# axiom_beta_sensor_cmv12000_tht_v0_16_r1_.net
KiCad netlist of a schematic drawn in EAGLE
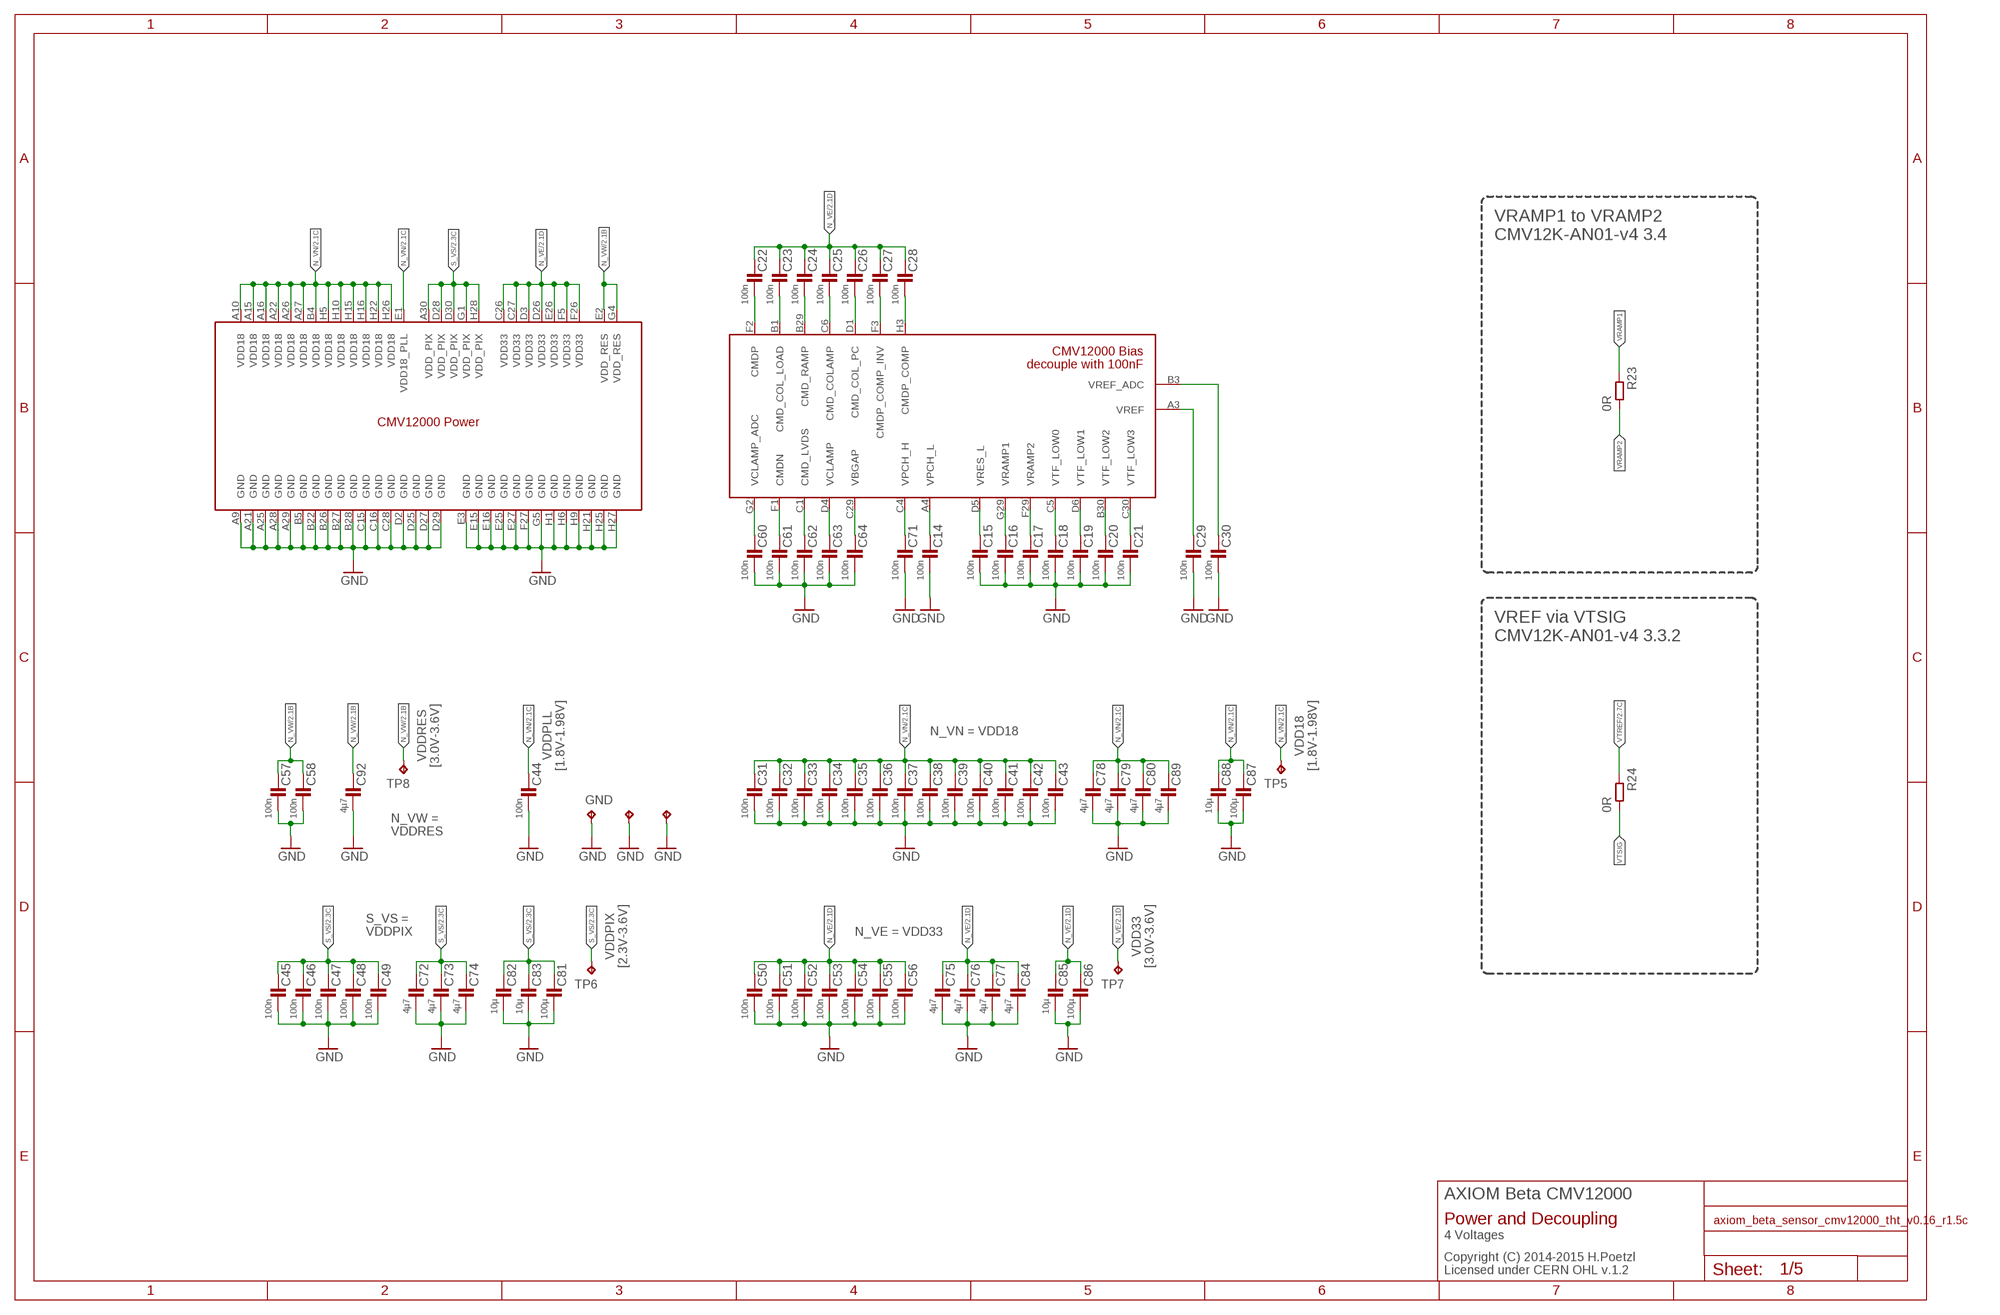
[diagram p0: schematic, sheet 1]
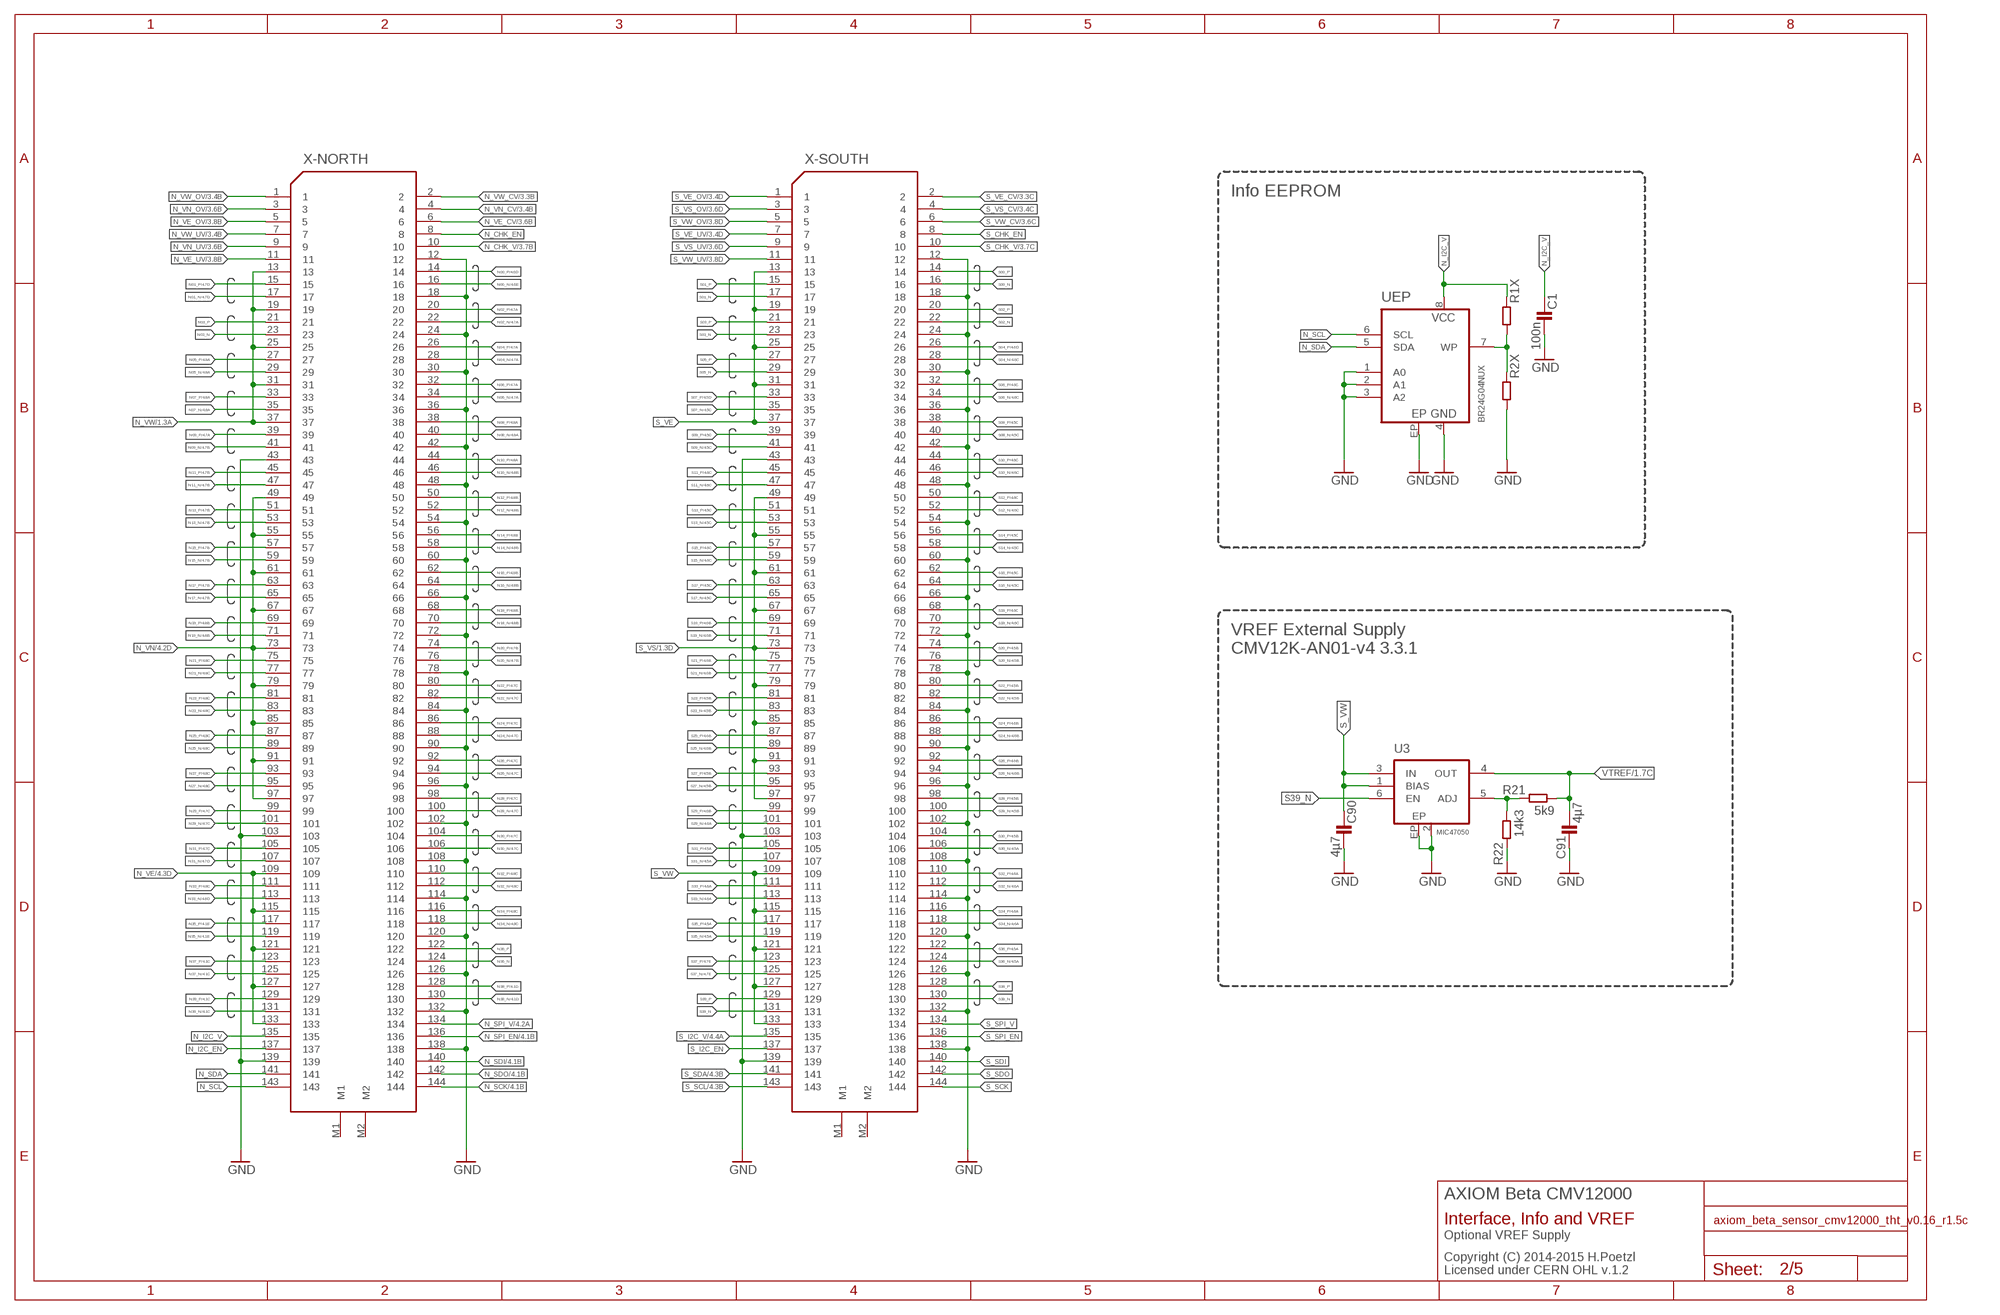
[diagram p1: schematic, sheet 2]
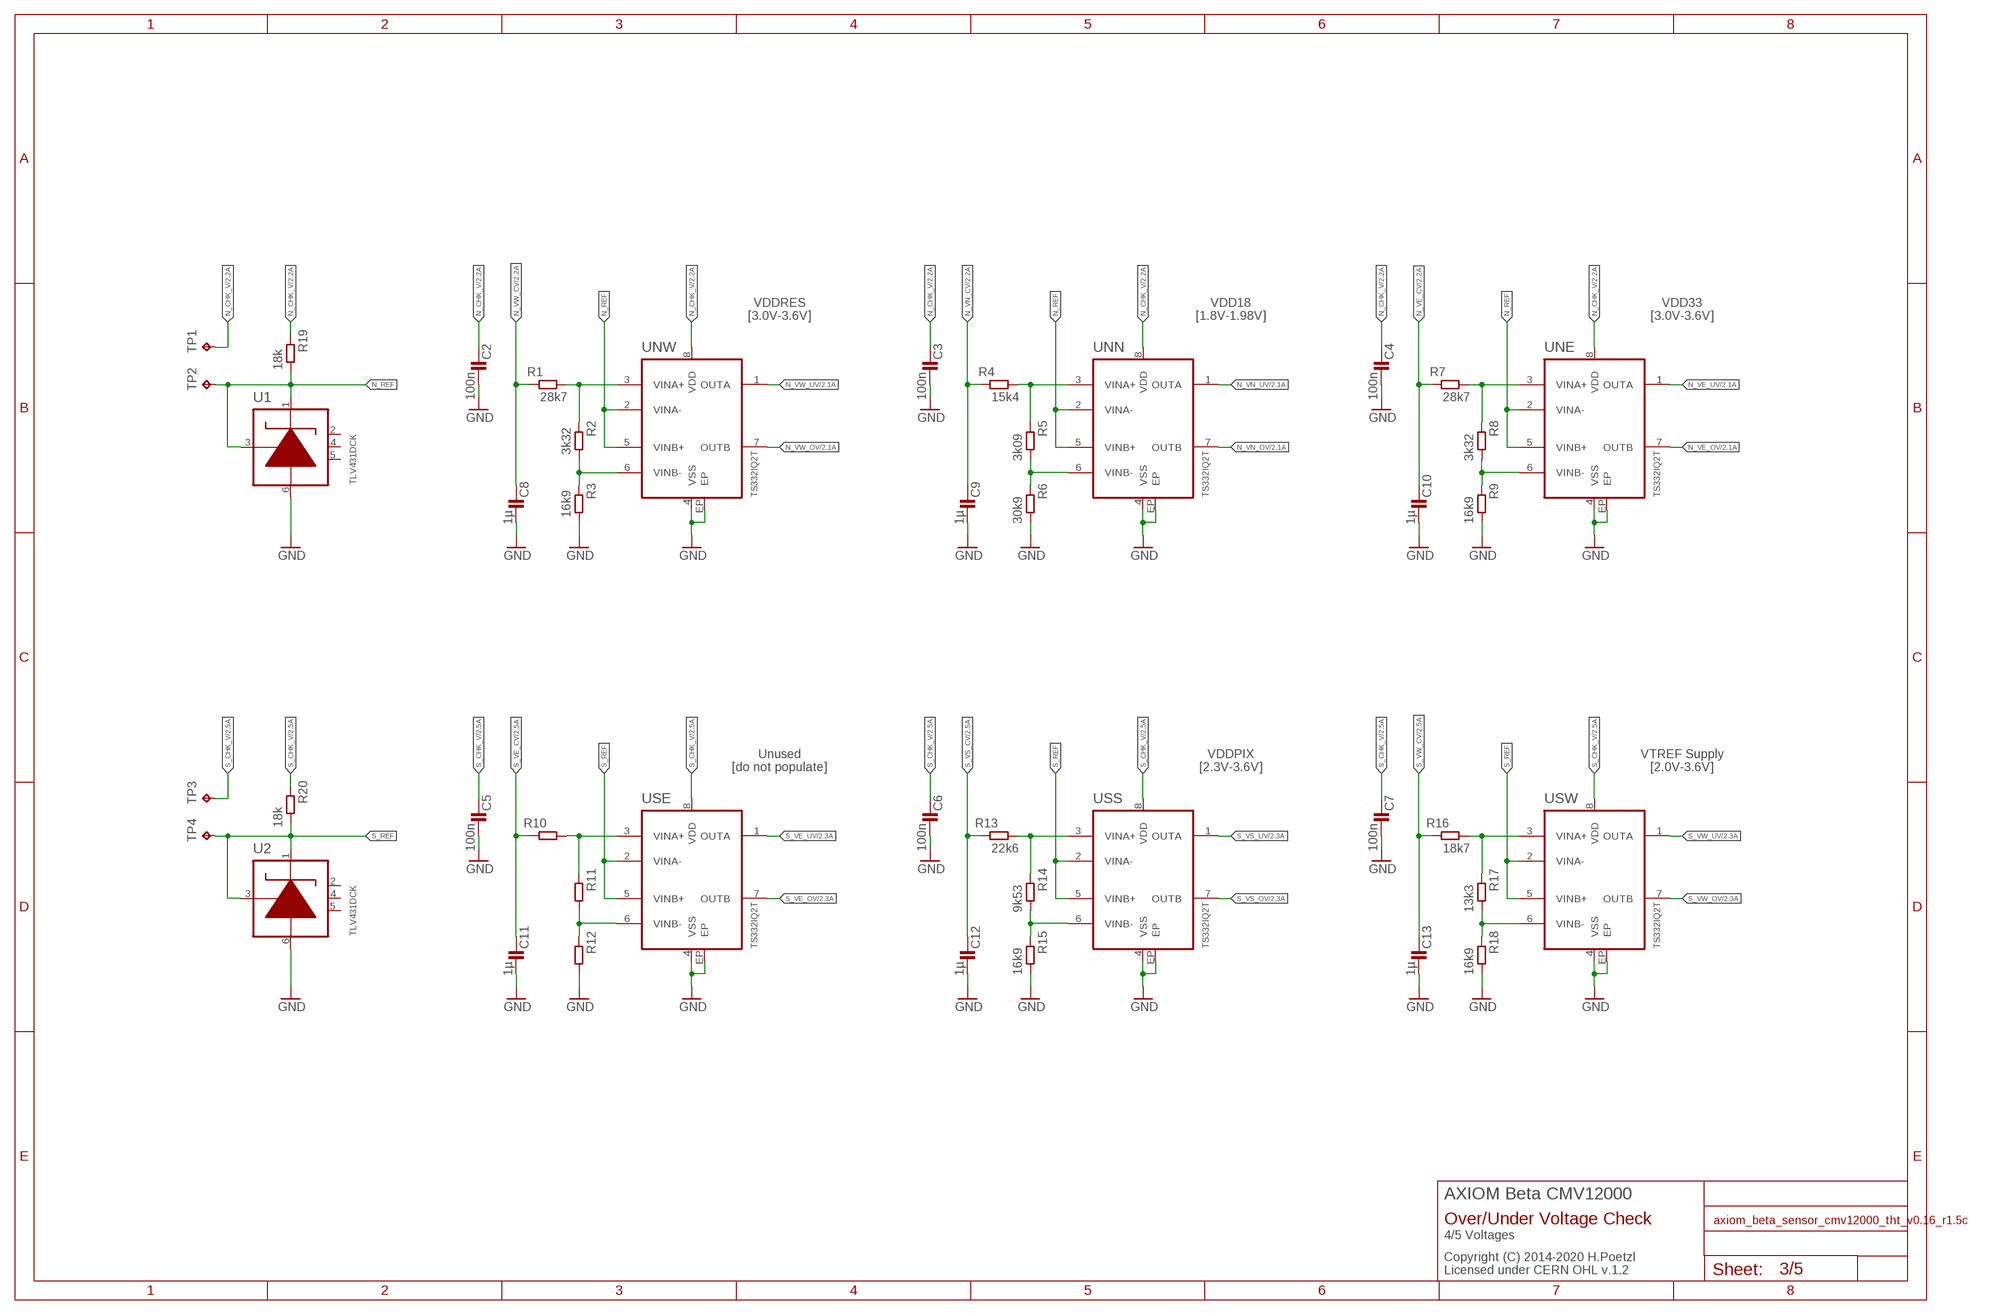
[diagram p2: schematic, sheet 3]
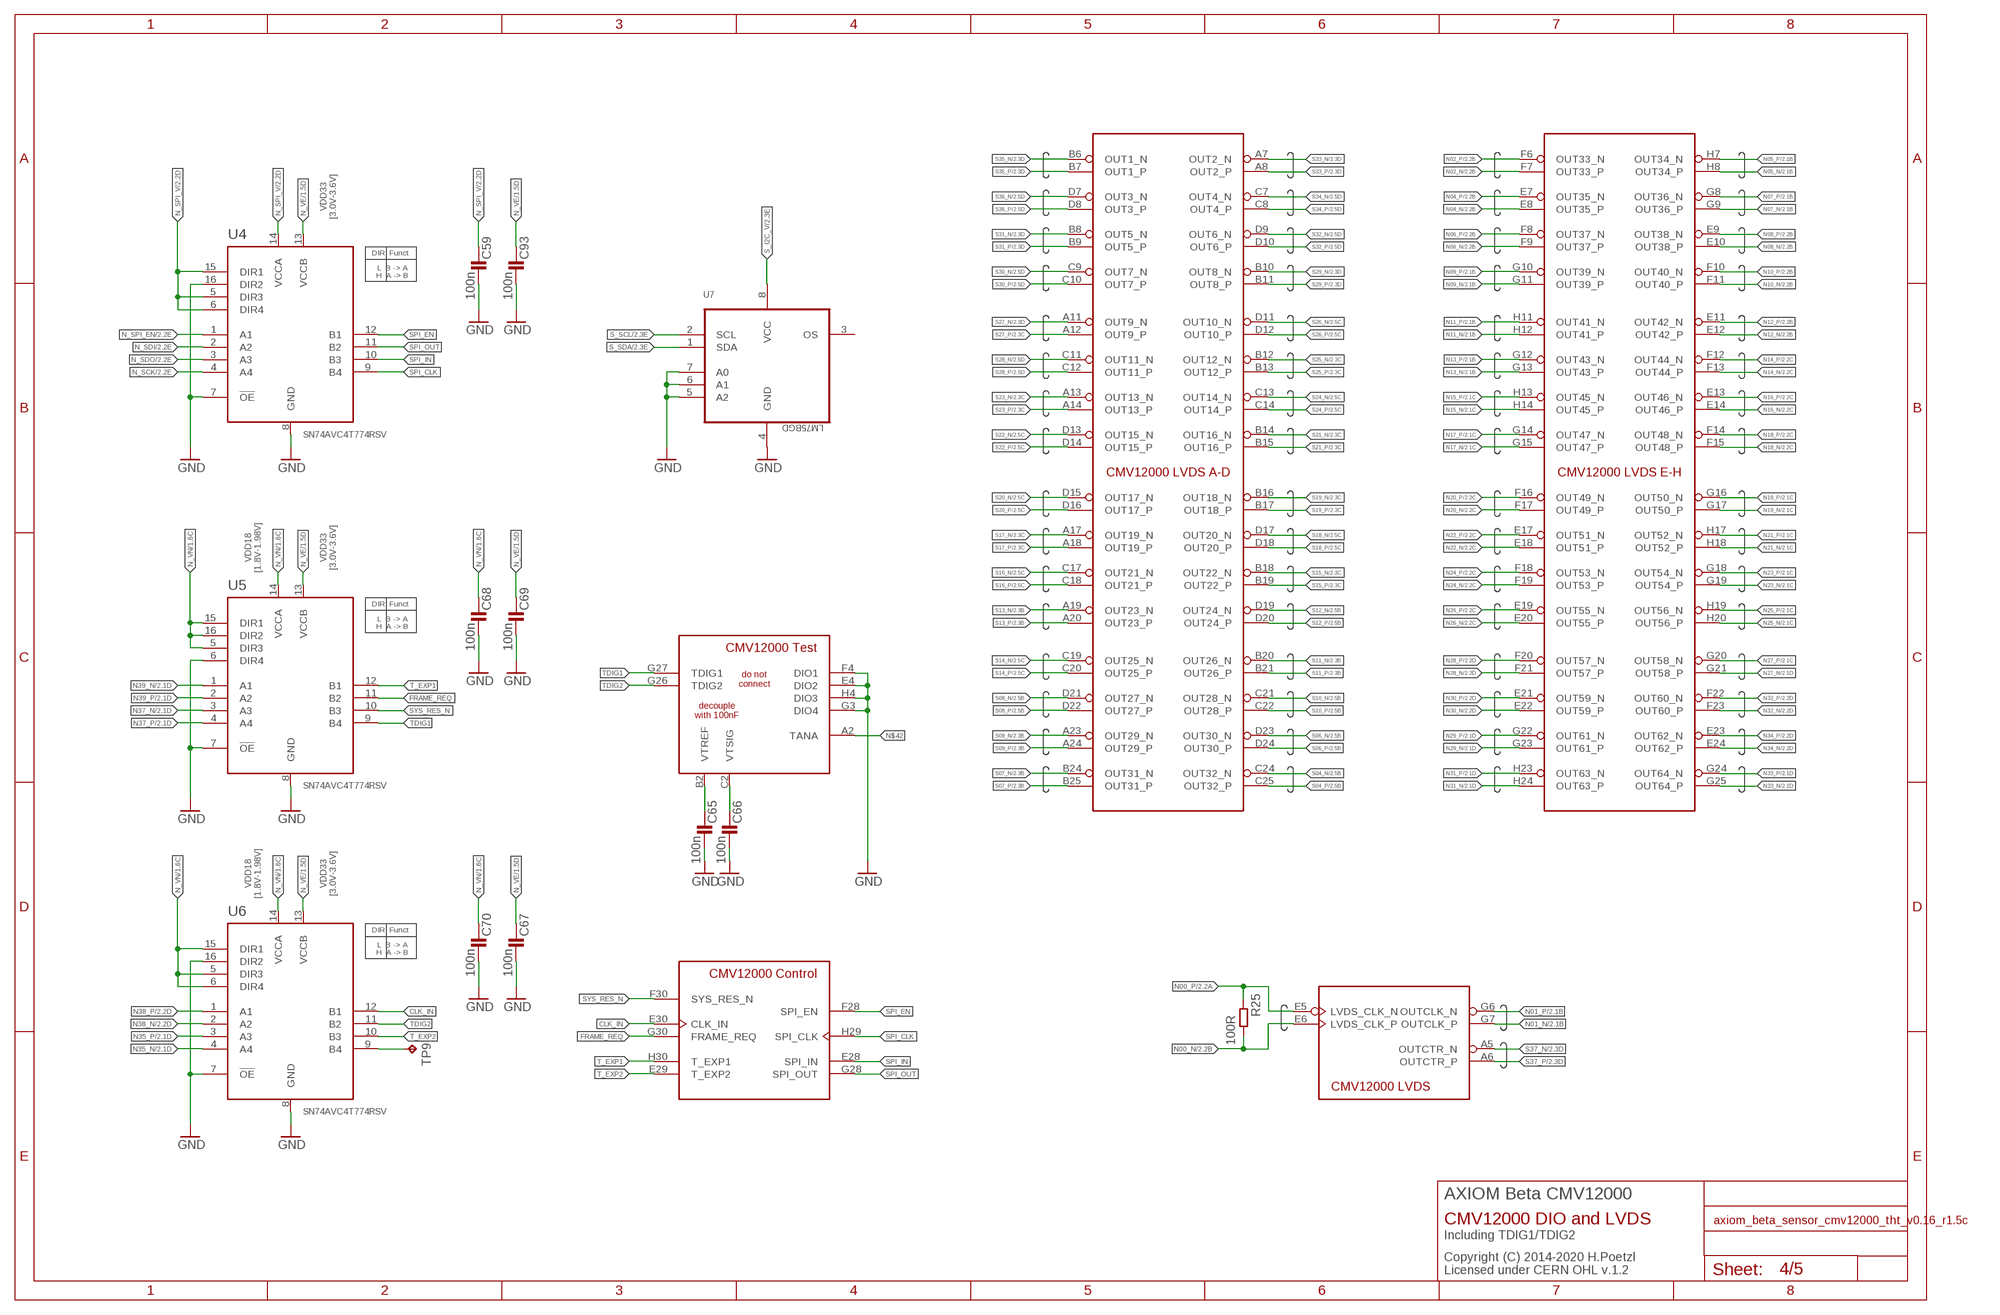
[diagram p3: schematic, sheet 4]
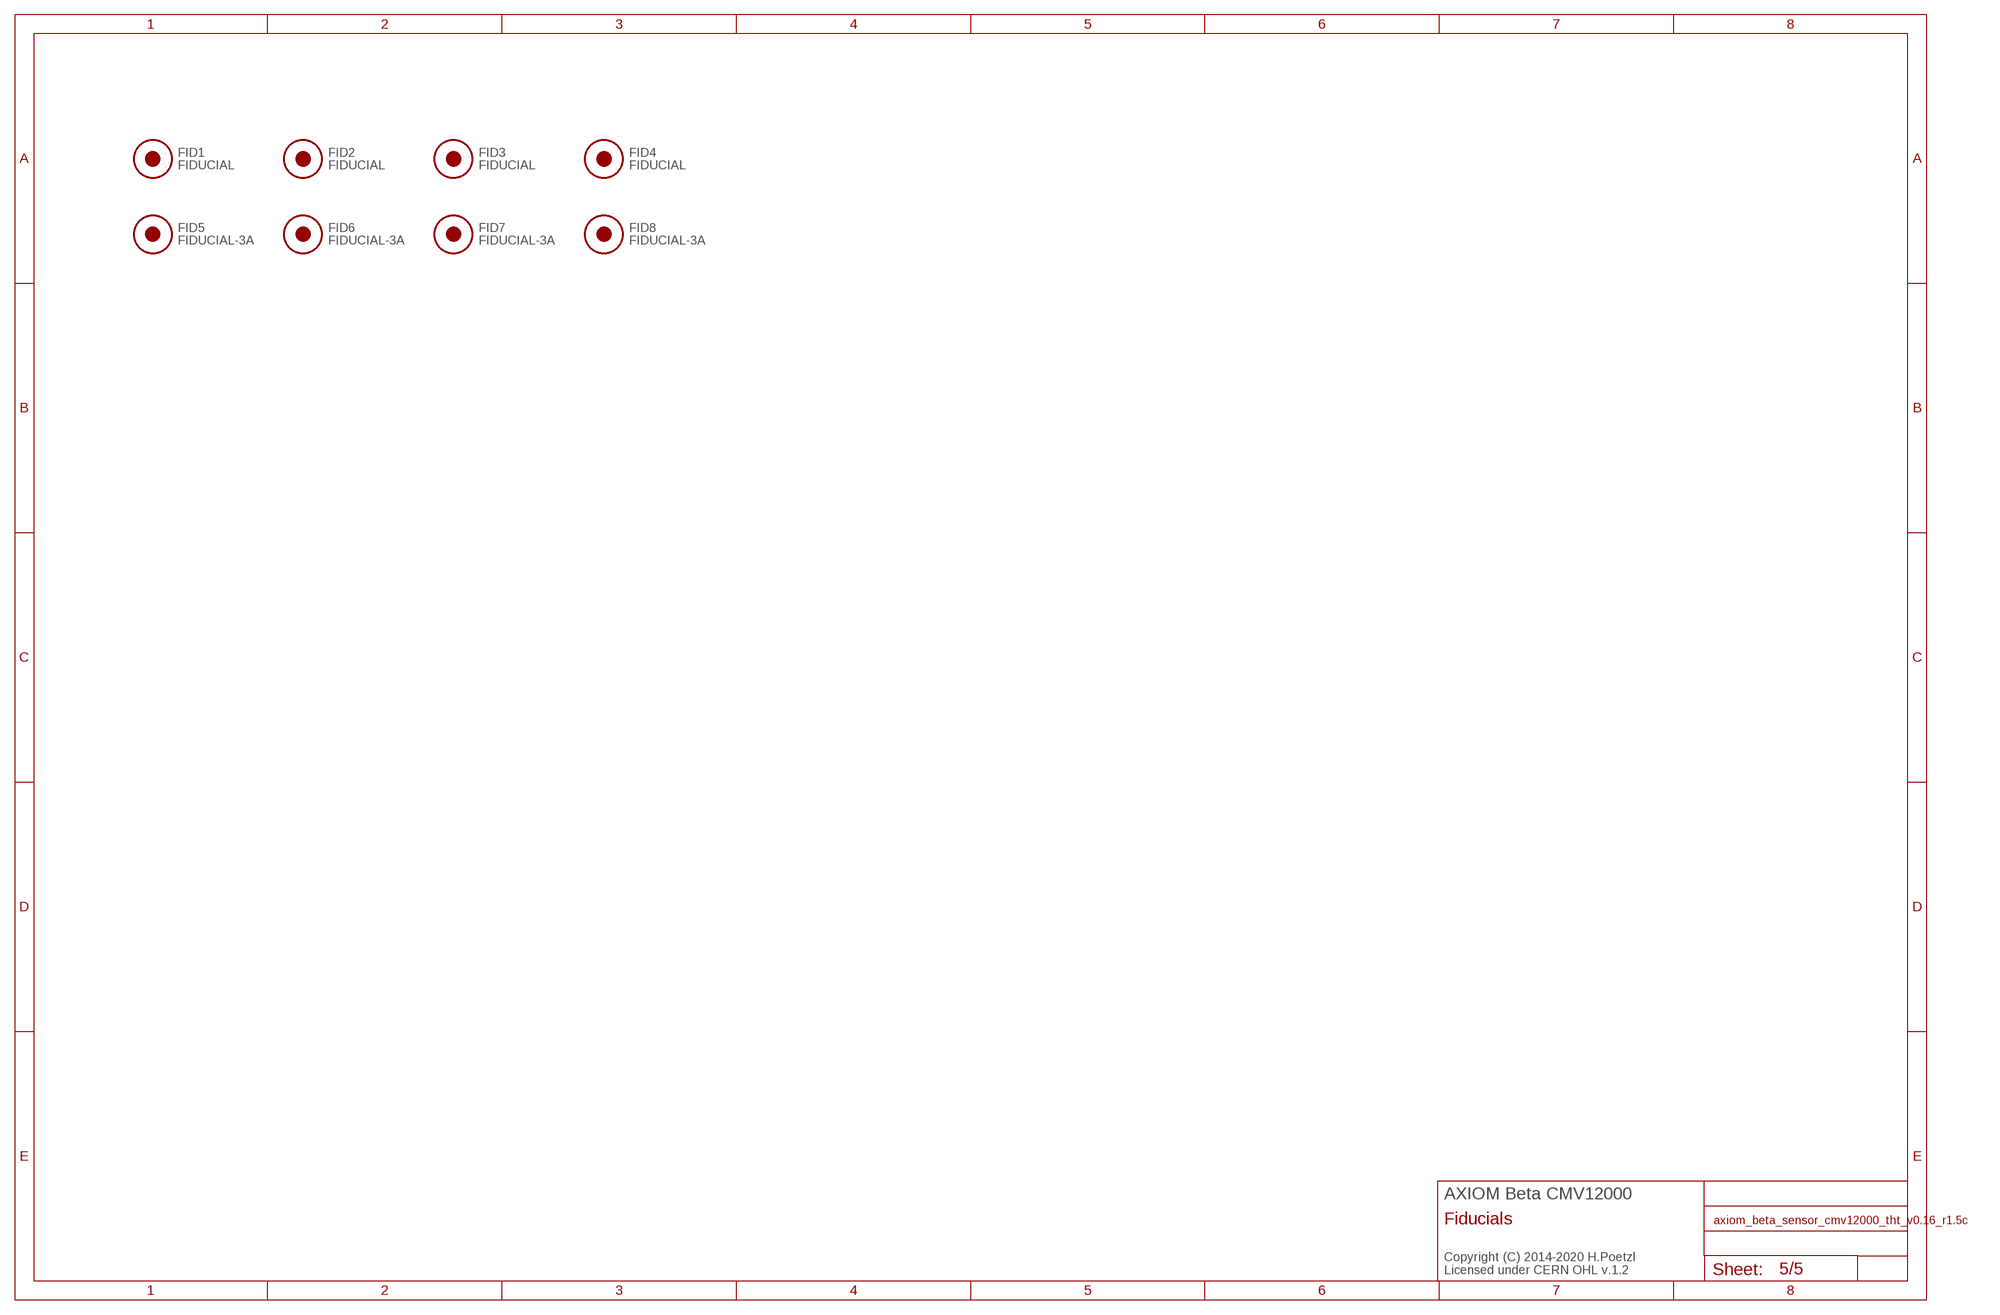
[diagram p4: schematic, sheet 5]

(export (version "E")
  (design (tool "Eeschema 10.0.6"))
  (components
    (comp (ref "FID1")
      (value "FIDUCIAL")
      (footprint "eagle-import:FID_ARROW")
      (libsource (lib "eagle-import") (part "FIDUCIAL"))
    )
    (comp (ref "FID2")
      (value "FIDUCIAL")
      (footprint "eagle-import:FID_ARROW")
      (libsource (lib "eagle-import") (part "FIDUCIAL"))
    )
    (comp (ref "FID3")
      (value "FIDUCIAL")
      (footprint "eagle-import:FID_ARROW")
      (libsource (lib "eagle-import") (part "FIDUCIAL"))
    )
    (comp (ref "FID4")
      (value "FIDUCIAL")
      (footprint "eagle-import:FID_ARROW")
      (libsource (lib "eagle-import") (part "FIDUCIAL"))
    )
    (comp (ref "FID5")
      (value "FIDUCIAL-3A")
      (footprint "eagle-import:FID_3ARROW")
      (libsource (lib "eagle-import") (part "FIDUCIAL-3A"))
    )
    (comp (ref "FID6")
      (value "FIDUCIAL-3A")
      (footprint "eagle-import:FID_3ARROW")
      (libsource (lib "eagle-import") (part "FIDUCIAL-3A"))
    )
    (comp (ref "FID7")
      (value "FIDUCIAL-3A")
      (footprint "eagle-import:FID_3ARROW")
      (libsource (lib "eagle-import") (part "FIDUCIAL-3A"))
    )
    (comp (ref "FID8")
      (value "FIDUCIAL-3A")
      (footprint "eagle-import:FID_3ARROW")
      (libsource (lib "eagle-import") (part "FIDUCIAL-3A"))
    )
    (comp (ref "C59")
      (value "100n")
      (footprint "eagle-import:0402-C")
      (libsource (lib "eagle-import") (part "C0402-C"))
    )
    (comp (ref "C65")
      (value "100n")
      (footprint "eagle-import:0402-C")
      (libsource (lib "eagle-import") (part "C0402-C"))
    )
    (comp (ref "C66")
      (value "100n")
      (footprint "eagle-import:0402-C")
      (libsource (lib "eagle-import") (part "C0402-C"))
    )
    (comp (ref "C67")
      (value "100n")
      (footprint "eagle-import:0402-C")
      (libsource (lib "eagle-import") (part "C0402-C"))
    )
    (comp (ref "C68")
      (value "100n")
      (footprint "eagle-import:0402-C")
      (libsource (lib "eagle-import") (part "C0402-C"))
    )
    (comp (ref "C69")
      (value "100n")
      (footprint "eagle-import:0402-C")
      (libsource (lib "eagle-import") (part "C0402-C"))
    )
    (comp (ref "C70")
      (value "100n")
      (footprint "eagle-import:0402-C")
      (libsource (lib "eagle-import") (part "C0402-C"))
    )
    (comp (ref "C93")
      (value "100n")
      (footprint "eagle-import:0402-C")
      (libsource (lib "eagle-import") (part "C0402-C"))
    )
    (comp (ref "R25")
      (value "100R")
      (footprint "eagle-import:0402-C")
      (libsource (lib "eagle-import") (part "R0402-C"))
    )
    (comp (ref "SENSOR")
      (value "CMV12000ANDON")
      (footprint "eagle-import:10-30-07-237-400T4")
      (libsource (lib "eagle-import") (part "CMV12000ANDON"))
    )
    (comp (ref "TP9")
      (value "TPTP10R")
      (footprint "eagle-import:TP10R")
      (libsource (lib "eagle-import") (part "TPTP10R"))
    )
    (comp (ref "U4")
      (value "SN74AVC4T774RSV")
      (footprint "eagle-import:QFN40P185X265X55-16N")
      (libsource (lib "eagle-import") (part "SN74AVC4T774RSV"))
    )
    (comp (ref "U5")
      (value "SN74AVC4T774RSV")
      (footprint "eagle-import:QFN40P185X265X55-16N")
      (libsource (lib "eagle-import") (part "SN74AVC4T774RSV"))
    )
    (comp (ref "U6")
      (value "SN74AVC4T774RSV")
      (footprint "eagle-import:QFN40P185X265X55-16N")
      (libsource (lib "eagle-import") (part "SN74AVC4T774RSV"))
    )
    (comp (ref "U7")
      (value "LM75BGD")
      (footprint "eagle-import:SOT996-2_3")
      (libsource (lib "eagle-import") (part "LM75BGD"))
    )
    (comp (ref "C14")
      (value "100n")
      (footprint "eagle-import:0402-C")
      (libsource (lib "eagle-import") (part "C0402-C"))
    )
    (comp (ref "C15")
      (value "100n")
      (footprint "eagle-import:0402-C")
      (libsource (lib "eagle-import") (part "C0402-C"))
    )
    (comp (ref "C16")
      (value "100n")
      (footprint "eagle-import:0402-C")
      (libsource (lib "eagle-import") (part "C0402-C"))
    )
    (comp (ref "C17")
      (value "100n")
      (footprint "eagle-import:0402-C")
      (libsource (lib "eagle-import") (part "C0402-C"))
    )
    (comp (ref "C18")
      (value "100n")
      (footprint "eagle-import:0402-C")
      (libsource (lib "eagle-import") (part "C0402-C"))
    )
    (comp (ref "C19")
      (value "100n")
      (footprint "eagle-import:0402-C")
      (libsource (lib "eagle-import") (part "C0402-C"))
    )
    (comp (ref "C20")
      (value "100n")
      (footprint "eagle-import:0402-C")
      (libsource (lib "eagle-import") (part "C0402-C"))
    )
    (comp (ref "C21")
      (value "100n")
      (footprint "eagle-import:0402-C")
      (libsource (lib "eagle-import") (part "C0402-C"))
    )
    (comp (ref "C22")
      (value "100n")
      (footprint "eagle-import:0402-C")
      (libsource (lib "eagle-import") (part "C0402-C"))
    )
    (comp (ref "C23")
      (value "100n")
      (footprint "eagle-import:0402-C")
      (libsource (lib "eagle-import") (part "C0402-C"))
    )
    (comp (ref "C24")
      (value "100n")
      (footprint "eagle-import:0402-C")
      (libsource (lib "eagle-import") (part "C0402-C"))
    )
    (comp (ref "C25")
      (value "100n")
      (footprint "eagle-import:0402-C")
      (libsource (lib "eagle-import") (part "C0402-C"))
    )
    (comp (ref "C26")
      (value "100n")
      (footprint "eagle-import:0402-C")
      (libsource (lib "eagle-import") (part "C0402-C"))
    )
    (comp (ref "C27")
      (value "100n")
      (footprint "eagle-import:0402-C")
      (libsource (lib "eagle-import") (part "C0402-C"))
    )
    (comp (ref "C28")
      (value "100n")
      (footprint "eagle-import:0402-C")
      (libsource (lib "eagle-import") (part "C0402-C"))
    )
    (comp (ref "C29")
      (value "100n")
      (footprint "eagle-import:0402-C")
      (libsource (lib "eagle-import") (part "C0402-C"))
    )
    (comp (ref "C30")
      (value "100n")
      (footprint "eagle-import:0402-C")
      (libsource (lib "eagle-import") (part "C0402-C"))
    )
    (comp (ref "C31")
      (value "100n")
      (footprint "eagle-import:0402-C")
      (libsource (lib "eagle-import") (part "C0402-C"))
    )
    (comp (ref "C32")
      (value "100n")
      (footprint "eagle-import:0402-C")
      (libsource (lib "eagle-import") (part "C0402-C"))
    )
    (comp (ref "C33")
      (value "100n")
      (footprint "eagle-import:0402-C")
      (libsource (lib "eagle-import") (part "C0402-C"))
    )
    (comp (ref "C34")
      (value "100n")
      (footprint "eagle-import:0402-C")
      (libsource (lib "eagle-import") (part "C0402-C"))
    )
    (comp (ref "C35")
      (value "100n")
      (footprint "eagle-import:0402-C")
      (libsource (lib "eagle-import") (part "C0402-C"))
    )
    (comp (ref "C36")
      (value "100n")
      (footprint "eagle-import:0402-C")
      (libsource (lib "eagle-import") (part "C0402-C"))
    )
    (comp (ref "C37")
      (value "100n")
      (footprint "eagle-import:0402-C")
      (libsource (lib "eagle-import") (part "C0402-C"))
    )
    (comp (ref "C38")
      (value "100n")
      (footprint "eagle-import:0402-C")
      (libsource (lib "eagle-import") (part "C0402-C"))
    )
    (comp (ref "C39")
      (value "100n")
      (footprint "eagle-import:0402-C")
      (libsource (lib "eagle-import") (part "C0402-C"))
    )
    (comp (ref "C40")
      (value "100n")
      (footprint "eagle-import:0402-C")
      (libsource (lib "eagle-import") (part "C0402-C"))
    )
    (comp (ref "C41")
      (value "100n")
      (footprint "eagle-import:0402-C")
      (libsource (lib "eagle-import") (part "C0402-C"))
    )
    (comp (ref "C42")
      (value "100n")
      (footprint "eagle-import:0402-C")
      (libsource (lib "eagle-import") (part "C0402-C"))
    )
    (comp (ref "C43")
      (value "100n")
      (footprint "eagle-import:0402-C")
      (libsource (lib "eagle-import") (part "C0402-C"))
    )
    (comp (ref "C44")
      (value "100n")
      (footprint "eagle-import:0402-C")
      (libsource (lib "eagle-import") (part "C0402-C"))
    )
    (comp (ref "C45")
      (value "100n")
      (footprint "eagle-import:0402-C")
      (libsource (lib "eagle-import") (part "C0402-C"))
    )
    (comp (ref "C46")
      (value "100n")
      (footprint "eagle-import:0402-C")
      (libsource (lib "eagle-import") (part "C0402-C"))
    )
    (comp (ref "C47")
      (value "100n")
      (footprint "eagle-import:0402-C")
      (libsource (lib "eagle-import") (part "C0402-C"))
    )
    (comp (ref "C48")
      (value "100n")
      (footprint "eagle-import:0402-C")
      (libsource (lib "eagle-import") (part "C0402-C"))
    )
    (comp (ref "C49")
      (value "100n")
      (footprint "eagle-import:0402-C")
      (libsource (lib "eagle-import") (part "C0402-C"))
    )
    (comp (ref "C50")
      (value "100n")
      (footprint "eagle-import:0402-C")
      (libsource (lib "eagle-import") (part "C0402-C"))
    )
    (comp (ref "C51")
      (value "100n")
      (footprint "eagle-import:0402-C")
      (libsource (lib "eagle-import") (part "C0402-C"))
    )
    (comp (ref "C52")
      (value "100n")
      (footprint "eagle-import:0402-C")
      (libsource (lib "eagle-import") (part "C0402-C"))
    )
    (comp (ref "C53")
      (value "100n")
      (footprint "eagle-import:0402-C")
      (libsource (lib "eagle-import") (part "C0402-C"))
    )
    (comp (ref "C54")
      (value "100n")
      (footprint "eagle-import:0402-C")
      (libsource (lib "eagle-import") (part "C0402-C"))
    )
    (comp (ref "C55")
      (value "100n")
      (footprint "eagle-import:0402-C")
      (libsource (lib "eagle-import") (part "C0402-C"))
    )
    (comp (ref "C56")
      (value "100n")
      (footprint "eagle-import:0402-C")
      (libsource (lib "eagle-import") (part "C0402-C"))
    )
    (comp (ref "C57")
      (value "100n")
      (footprint "eagle-import:0402-C")
      (libsource (lib "eagle-import") (part "C0402-C"))
    )
    (comp (ref "C58")
      (value "100n")
      (footprint "eagle-import:0402-C")
      (libsource (lib "eagle-import") (part "C0402-C"))
    )
    (comp (ref "C60")
      (value "100n")
      (footprint "eagle-import:0402-C")
      (libsource (lib "eagle-import") (part "C0402-C"))
    )
    (comp (ref "C61")
      (value "100n")
      (footprint "eagle-import:0402-C")
      (libsource (lib "eagle-import") (part "C0402-C"))
    )
    (comp (ref "C62")
      (value "100n")
      (footprint "eagle-import:0402-C")
      (libsource (lib "eagle-import") (part "C0402-C"))
    )
    (comp (ref "C63")
      (value "100n")
      (footprint "eagle-import:0402-C")
      (libsource (lib "eagle-import") (part "C0402-C"))
    )
    (comp (ref "C64")
      (value "100n")
      (footprint "eagle-import:0402-C")
      (libsource (lib "eagle-import") (part "C0402-C"))
    )
    (comp (ref "C71")
      (value "100n")
      (footprint "eagle-import:0402-C")
      (libsource (lib "eagle-import") (part "C0402-C"))
    )
    (comp (ref "C72")
      (value "4µ7")
      (footprint "eagle-import:0402-B")
      (libsource (lib "eagle-import") (part "C0402-B"))
    )
    (comp (ref "C73")
      (value "4µ7")
      (footprint "eagle-import:0402-C")
      (libsource (lib "eagle-import") (part "C0402-C"))
    )
    (comp (ref "C74")
      (value "4µ7")
      (footprint "eagle-import:0402-C")
      (libsource (lib "eagle-import") (part "C0402-C"))
    )
    (comp (ref "C75")
      (value "4µ7")
      (footprint "eagle-import:0402-C")
      (libsource (lib "eagle-import") (part "C0402-C"))
    )
    (comp (ref "C76")
      (value "4µ7")
      (footprint "eagle-import:0402-C")
      (libsource (lib "eagle-import") (part "C0402-C"))
    )
    (comp (ref "C77")
      (value "4µ7")
      (footprint "eagle-import:0402-B")
      (libsource (lib "eagle-import") (part "C0402-B"))
    )
    (comp (ref "C78")
      (value "4µ7")
      (footprint "eagle-import:0402-B")
      (libsource (lib "eagle-import") (part "C0402-B"))
    )
    (comp (ref "C79")
      (value "4µ7")
      (footprint "eagle-import:0402-C")
      (libsource (lib "eagle-import") (part "C0402-C"))
    )
    (comp (ref "C80")
      (value "4µ7")
      (footprint "eagle-import:0402-C")
      (libsource (lib "eagle-import") (part "C0402-C"))
    )
    (comp (ref "C81")
      (value "100µ")
      (footprint "eagle-import:1206-B")
      (libsource (lib "eagle-import") (part "C1206-B"))
    )
    (comp (ref "C82")
      (value "10µ")
      (footprint "eagle-import:0603-C")
      (libsource (lib "eagle-import") (part "C0603-C"))
    )
    (comp (ref "C83")
      (value "10µ")
      (footprint "eagle-import:0603-C")
      (libsource (lib "eagle-import") (part "C0603-C"))
    )
    (comp (ref "C84")
      (value "4µ7")
      (footprint "eagle-import:0402-C")
      (libsource (lib "eagle-import") (part "C0402-C"))
    )
    (comp (ref "C85")
      (value "10µ")
      (footprint "eagle-import:0603-C")
      (libsource (lib "eagle-import") (part "C0603-C"))
    )
    (comp (ref "C86")
      (value "100µ")
      (footprint "eagle-import:1206-B")
      (libsource (lib "eagle-import") (part "C1206-B"))
    )
    (comp (ref "C87")
      (value "100µ")
      (footprint "eagle-import:1206-B")
      (libsource (lib "eagle-import") (part "C1206-B"))
    )
    (comp (ref "C88")
      (value "10µ")
      (footprint "eagle-import:0603-C")
      (libsource (lib "eagle-import") (part "C0603-C"))
    )
    (comp (ref "C89")
      (value "4µ7")
      (footprint "eagle-import:0402-C")
      (libsource (lib "eagle-import") (part "C0402-C"))
    )
    (comp (ref "C92")
      (value "4µ7")
      (footprint "eagle-import:0402-C")
      (libsource (lib "eagle-import") (part "C0402-C"))
    )
    (comp (ref "GND")
      (value "TPTP10R")
      (footprint "eagle-import:TP10R")
      (libsource (lib "eagle-import") (part "TPTP10R"))
    )
    (comp (ref "GND75")
      (value "TPTP10R")
      (footprint "eagle-import:TP10R")
      (libsource (lib "eagle-import") (part "TPTP10R"))
    )
    (comp (ref "GND77")
      (value "TPTP10R")
      (footprint "eagle-import:TP10R")
      (libsource (lib "eagle-import") (part "TPTP10R"))
    )
    (comp (ref "R23")
      (value "0R")
      (footprint "eagle-import:0402-C")
      (libsource (lib "eagle-import") (part "R0402-C"))
    )
    (comp (ref "R24")
      (value "0R")
      (footprint "eagle-import:0402-C")
      (libsource (lib "eagle-import") (part "R0402-C"))
    )
    (comp (ref "TP5")
      (value "TPTP10R")
      (footprint "eagle-import:TP10R")
      (libsource (lib "eagle-import") (part "TPTP10R"))
    )
    (comp (ref "TP6")
      (value "TPTP10R")
      (footprint "eagle-import:TP10R")
      (libsource (lib "eagle-import") (part "TPTP10R"))
    )
    (comp (ref "TP7")
      (value "TPTP10R")
      (footprint "eagle-import:TP10R")
      (libsource (lib "eagle-import") (part "TPTP10R"))
    )
    (comp (ref "TP8")
      (value "TPTP10R")
      (footprint "eagle-import:TP10R")
      (libsource (lib "eagle-import") (part "TPTP10R"))
    )
    (comp (ref "C1")
      (value "100n")
      (footprint "eagle-import:0402-C")
      (libsource (lib "eagle-import") (part "C0402-C"))
    )
    (comp (ref "C90")
      (value "4µ7")
      (footprint "eagle-import:0402-C")
      (libsource (lib "eagle-import") (part "C0402-C"))
    )
    (comp (ref "C91")
      (value "4µ7")
      (footprint "eagle-import:0402-C")
      (libsource (lib "eagle-import") (part "C0402-C"))
    )
    (comp (ref "R1X")
      (value "R0402-C")
      (footprint "eagle-import:0402-C")
      (libsource (lib "eagle-import") (part "R0402-C"))
    )
    (comp (ref "R2X")
      (value "R0402-C")
      (footprint "eagle-import:0402-C")
      (libsource (lib "eagle-import") (part "R0402-C"))
    )
    (comp (ref "R21")
      (value "5k9")
      (footprint "eagle-import:0402-C")
      (libsource (lib "eagle-import") (part "R0402-C"))
    )
    (comp (ref "R22")
      (value "14k3")
      (footprint "eagle-import:0402-C")
      (libsource (lib "eagle-import") (part "R0402-C"))
    )
    (comp (ref "U3")
      (value "MIC47050")
      (footprint "eagle-import:MLF-6")
      (libsource (lib "eagle-import") (part "MIC47050-ADJ"))
    )
    (comp (ref "UEP")
      (value "BR24G04NUX")
      (footprint "eagle-import:DFN200X300X100-9N")
      (libsource (lib "eagle-import") (part "BR24G04NUX"))
    )
    (comp (ref "X-NORTH")
      (value "FX10-144P")
      (footprint "eagle-import:FX10A-144P")
      (libsource (lib "eagle-import") (part "FX10-144P"))
    )
    (comp (ref "X-SOUTH")
      (value "FX10-144P")
      (footprint "eagle-import:FX10A-144P")
      (libsource (lib "eagle-import") (part "FX10-144P"))
    )
    (comp (ref "C2")
      (value "100n")
      (footprint "eagle-import:0402-C")
      (libsource (lib "eagle-import") (part "C0402-C"))
    )
    (comp (ref "C3")
      (value "100n")
      (footprint "eagle-import:0402-C")
      (libsource (lib "eagle-import") (part "C0402-C"))
    )
    (comp (ref "C4")
      (value "100n")
      (footprint "eagle-import:0402-C")
      (libsource (lib "eagle-import") (part "C0402-C"))
    )
    (comp (ref "C5")
      (value "100n")
      (footprint "eagle-import:0402-C")
      (libsource (lib "eagle-import") (part "C0402-C"))
    )
    (comp (ref "C6")
      (value "100n")
      (footprint "eagle-import:0402-C")
      (libsource (lib "eagle-import") (part "C0402-C"))
    )
    (comp (ref "C7")
      (value "100n")
      (footprint "eagle-import:0402-C")
      (libsource (lib "eagle-import") (part "C0402-C"))
    )
    (comp (ref "C8")
      (value "1µ")
      (footprint "eagle-import:0402-C")
      (libsource (lib "eagle-import") (part "C0402-C"))
    )
    (comp (ref "C9")
      (value "1µ")
      (footprint "eagle-import:0402-C")
      (libsource (lib "eagle-import") (part "C0402-C"))
    )
    (comp (ref "C10")
      (value "1µ")
      (footprint "eagle-import:0402-C")
      (libsource (lib "eagle-import") (part "C0402-C"))
    )
    (comp (ref "C11")
      (value "1µ")
      (footprint "eagle-import:0402-C")
      (libsource (lib "eagle-import") (part "C0402-C"))
    )
    (comp (ref "C12")
      (value "1µ")
      (footprint "eagle-import:0402-C")
      (libsource (lib "eagle-import") (part "C0402-C"))
    )
    (comp (ref "C13")
      (value "1µ")
      (footprint "eagle-import:0402-C")
      (libsource (lib "eagle-import") (part "C0402-C"))
    )
    (comp (ref "R1")
      (value "28k7")
      (footprint "eagle-import:0402-C")
      (libsource (lib "eagle-import") (part "R0402-C"))
    )
    (comp (ref "R2")
      (value "3k32")
      (footprint "eagle-import:0402-C")
      (libsource (lib "eagle-import") (part "R0402-C"))
    )
    (comp (ref "R3")
      (value "16k9")
      (footprint "eagle-import:0402-C")
      (libsource (lib "eagle-import") (part "R0402-C"))
    )
    (comp (ref "R4")
      (value "15k4")
      (footprint "eagle-import:0402-C")
      (libsource (lib "eagle-import") (part "R0402-C"))
    )
    (comp (ref "R5")
      (value "3k09")
      (footprint "eagle-import:0402-C")
      (libsource (lib "eagle-import") (part "R0402-C"))
    )
    (comp (ref "R6")
      (value "30k9")
      (footprint "eagle-import:0402-C")
      (libsource (lib "eagle-import") (part "R0402-C"))
    )
    (comp (ref "R7")
      (value "28k7")
      (footprint "eagle-import:0402-C")
      (libsource (lib "eagle-import") (part "R0402-C"))
    )
    (comp (ref "R8")
      (value "3k32")
      (footprint "eagle-import:0402-C")
      (libsource (lib "eagle-import") (part "R0402-C"))
    )
    (comp (ref "R9")
      (value "16k9")
      (footprint "eagle-import:0402-C")
      (libsource (lib "eagle-import") (part "R0402-C"))
    )
    (comp (ref "R10")
      (value "R0402-C")
      (footprint "eagle-import:0402-C")
      (libsource (lib "eagle-import") (part "R0402-C"))
    )
    (comp (ref "R11")
      (value "R0402-C")
      (footprint "eagle-import:0402-C")
      (libsource (lib "eagle-import") (part "R0402-C"))
    )
    (comp (ref "R12")
      (value "R0402-C")
      (footprint "eagle-import:0402-C")
      (libsource (lib "eagle-import") (part "R0402-C"))
    )
    (comp (ref "R13")
      (value "22k6")
      (footprint "eagle-import:0402-C")
      (libsource (lib "eagle-import") (part "R0402-C"))
    )
    (comp (ref "R14")
      (value "9k53")
      (footprint "eagle-import:0402-C")
      (libsource (lib "eagle-import") (part "R0402-C"))
    )
    (comp (ref "R15")
      (value "16k9")
      (footprint "eagle-import:0402-C")
      (libsource (lib "eagle-import") (part "R0402-C"))
    )
    (comp (ref "R16")
      (value "18k7")
      (footprint "eagle-import:0402-C")
      (libsource (lib "eagle-import") (part "R0402-C"))
    )
    (comp (ref "R17")
      (value "13k3")
      (footprint "eagle-import:0402-C")
      (libsource (lib "eagle-import") (part "R0402-C"))
    )
    (comp (ref "R18")
      (value "16k9")
      (footprint "eagle-import:0402-C")
      (libsource (lib "eagle-import") (part "R0402-C"))
    )
    (comp (ref "R19")
      (value "18k")
      (footprint "eagle-import:0402-C")
      (libsource (lib "eagle-import") (part "R0402-C"))
    )
    (comp (ref "R20")
      (value "18k")
      (footprint "eagle-import:0402-C")
      (libsource (lib "eagle-import") (part "R0402-C"))
    )
    (comp (ref "TP1")
      (value "TPTP10R")
      (footprint "eagle-import:TP10R")
      (libsource (lib "eagle-import") (part "TPTP10R"))
    )
    (comp (ref "TP2")
      (value "TPTP10R")
      (footprint "eagle-import:TP10R")
      (libsource (lib "eagle-import") (part "TPTP10R"))
    )
    (comp (ref "TP3")
      (value "TPTP10R")
      (footprint "eagle-import:TP10R")
      (libsource (lib "eagle-import") (part "TPTP10R"))
    )
    (comp (ref "TP4")
      (value "TPTP10R")
      (footprint "eagle-import:TP10R")
      (libsource (lib "eagle-import") (part "TPTP10R"))
    )
    (comp (ref "U1")
      (value "TLV431DCK")
      (footprint "eagle-import:SOT65P210X110-6N")
      (libsource (lib "eagle-import") (part "TLV431DCK"))
    )
    (comp (ref "U2")
      (value "TLV431DCK")
      (footprint "eagle-import:SOT65P210X110-6N")
      (libsource (lib "eagle-import") (part "TLV431DCK"))
    )
    (comp (ref "UNE")
      (value "TS332IQ2T")
      (footprint "eagle-import:DFN200X200X100-9N")
      (libsource (lib "eagle-import") (part "TS332IQ2T"))
    )
    (comp (ref "UNN")
      (value "TS332IQ2T")
      (footprint "eagle-import:DFN200X200X100-9N")
      (libsource (lib "eagle-import") (part "TS332IQ2T"))
    )
    (comp (ref "UNW")
      (value "TS332IQ2T")
      (footprint "eagle-import:DFN200X200X100-9N")
      (libsource (lib "eagle-import") (part "TS332IQ2T"))
    )
    (comp (ref "USE")
      (value "TS332IQ2T")
      (footprint "eagle-import:DFN200X200X100-9N")
      (libsource (lib "eagle-import") (part "TS332IQ2T"))
    )
    (comp (ref "USS")
      (value "TS332IQ2T")
      (footprint "eagle-import:DFN200X200X100-9N")
      (libsource (lib "eagle-import") (part "TS332IQ2T"))
    )
    (comp (ref "USW")
      (value "TS332IQ2T")
      (footprint "eagle-import:DFN200X200X100-9N")
      (libsource (lib "eagle-import") (part "TS332IQ2T"))
    )
  )
  (nets
    (net (code "1") (name "CLK_IN") (class "Default")
      (node (ref "SENSOR") (pin "E30") (pinfunction "CLK_IN_E30") (pintype "input"))
      (node (ref "U6") (pin "12") (pinfunction "B1_12") (pintype "bidirectional"))
    )
    (net (code "2") (name "FRAME_REQ") (class "Default")
      (node (ref "SENSOR") (pin "G30") (pinfunction "FRAME_REQ_G30") (pintype "input"))
      (node (ref "U5") (pin "11") (pinfunction "B2_11") (pintype "bidirectional"))
    )
    (net (code "3") (name "GND") (class "Default")
      (node (ref "C1") (pin "2") (pinfunction "2_2") (pintype "passive"))
      (node (ref "C10") (pin "2") (pinfunction "2_2") (pintype "passive"))
      (node (ref "C11") (pin "2") (pinfunction "2_2") (pintype "passive"))
      (node (ref "C12") (pin "2") (pinfunction "2_2") (pintype "passive"))
      (node (ref "C13") (pin "2") (pinfunction "2_2") (pintype "passive"))
      (node (ref "C14") (pin "2") (pinfunction "2_2") (pintype "passive"))
      (node (ref "C15") (pin "2") (pinfunction "2_2") (pintype "passive"))
      (node (ref "C16") (pin "2") (pinfunction "2_2") (pintype "passive"))
      (node (ref "C17") (pin "2") (pinfunction "2_2") (pintype "passive"))
      (node (ref "C18") (pin "2") (pinfunction "2_2") (pintype "passive"))
      (node (ref "C19") (pin "2") (pinfunction "2_2") (pintype "passive"))
      (node (ref "C2") (pin "2") (pinfunction "2_2") (pintype "passive"))
      (node (ref "C20") (pin "2") (pinfunction "2_2") (pintype "passive"))
      (node (ref "C21") (pin "2") (pinfunction "2_2") (pintype "passive"))
      (node (ref "C29") (pin "2") (pinfunction "2_2") (pintype "passive"))
      (node (ref "C3") (pin "2") (pinfunction "2_2") (pintype "passive"))
      (node (ref "C30") (pin "2") (pinfunction "2_2") (pintype "passive"))
      (node (ref "C31") (pin "2") (pinfunction "2_2") (pintype "passive"))
      (node (ref "C32") (pin "2") (pinfunction "2_2") (pintype "passive"))
      (node (ref "C33") (pin "2") (pinfunction "2_2") (pintype "passive"))
      (node (ref "C34") (pin "2") (pinfunction "2_2") (pintype "passive"))
      (node (ref "C35") (pin "2") (pinfunction "2_2") (pintype "passive"))
      (node (ref "C36") (pin "2") (pinfunction "2_2") (pintype "passive"))
      (node (ref "C37") (pin "2") (pinfunction "2_2") (pintype "passive"))
      (node (ref "C38") (pin "2") (pinfunction "2_2") (pintype "passive"))
      (node (ref "C39") (pin "2") (pinfunction "2_2") (pintype "passive"))
      (node (ref "C4") (pin "2") (pinfunction "2_2") (pintype "passive"))
      (node (ref "C40") (pin "2") (pinfunction "2_2") (pintype "passive"))
      (node (ref "C41") (pin "2") (pinfunction "2_2") (pintype "passive"))
      (node (ref "C42") (pin "2") (pinfunction "2_2") (pintype "passive"))
      (node (ref "C43") (pin "2") (pinfunction "2_2") (pintype "passive"))
      (node (ref "C44") (pin "2") (pinfunction "2_2") (pintype "passive"))
      (node (ref "C45") (pin "2") (pinfunction "2_2") (pintype "passive"))
      (node (ref "C46") (pin "2") (pinfunction "2_2") (pintype "passive"))
      (node (ref "C47") (pin "2") (pinfunction "2_2") (pintype "passive"))
      (node (ref "C48") (pin "2") (pinfunction "2_2") (pintype "passive"))
      (node (ref "C49") (pin "2") (pinfunction "2_2") (pintype "passive"))
      (node (ref "C5") (pin "2") (pinfunction "2_2") (pintype "passive"))
      (node (ref "C50") (pin "2") (pinfunction "2_2") (pintype "passive"))
      (node (ref "C51") (pin "2") (pinfunction "2_2") (pintype "passive"))
      (node (ref "C52") (pin "2") (pinfunction "2_2") (pintype "passive"))
      (node (ref "C53") (pin "2") (pinfunction "2_2") (pintype "passive"))
      (node (ref "C54") (pin "2") (pinfunction "2_2") (pintype "passive"))
      (node (ref "C55") (pin "2") (pinfunction "2_2") (pintype "passive"))
      (node (ref "C56") (pin "2") (pinfunction "2_2") (pintype "passive"))
      (node (ref "C57") (pin "2") (pinfunction "2_2") (pintype "passive"))
      (node (ref "C58") (pin "2") (pinfunction "2_2") (pintype "passive"))
      (node (ref "C59") (pin "2") (pinfunction "2_2") (pintype "passive"))
      (node (ref "C6") (pin "2") (pinfunction "2_2") (pintype "passive"))
      (node (ref "C60") (pin "2") (pinfunction "2_2") (pintype "passive"))
      (node (ref "C61") (pin "2") (pinfunction "2_2") (pintype "passive"))
      (node (ref "C62") (pin "2") (pinfunction "2_2") (pintype "passive"))
      (node (ref "C63") (pin "2") (pinfunction "2_2") (pintype "passive"))
      (node (ref "C64") (pin "2") (pinfunction "2_2") (pintype "passive"))
      (node (ref "C65") (pin "2") (pinfunction "2_2") (pintype "passive"))
      (node (ref "C66") (pin "2") (pinfunction "2_2") (pintype "passive"))
      (node (ref "C67") (pin "2") (pinfunction "2_2") (pintype "passive"))
      (node (ref "C68") (pin "2") (pinfunction "2_2") (pintype "passive"))
      (node (ref "C69") (pin "2") (pinfunction "2_2") (pintype "passive"))
      (node (ref "C7") (pin "2") (pinfunction "2_2") (pintype "passive"))
      (node (ref "C70") (pin "2") (pinfunction "2_2") (pintype "passive"))
      (node (ref "C71") (pin "2") (pinfunction "2_2") (pintype "passive"))
      (node (ref "C72") (pin "2") (pinfunction "2_2") (pintype "passive"))
      (node (ref "C73") (pin "2") (pinfunction "2_2") (pintype "passive"))
      (node (ref "C74") (pin "2") (pinfunction "2_2") (pintype "passive"))
      (node (ref "C75") (pin "2") (pinfunction "2_2") (pintype "passive"))
      (node (ref "C76") (pin "2") (pinfunction "2_2") (pintype "passive"))
      (node (ref "C77") (pin "2") (pinfunction "2_2") (pintype "passive"))
      (node (ref "C78") (pin "2") (pinfunction "2_2") (pintype "passive"))
      (node (ref "C79") (pin "2") (pinfunction "2_2") (pintype "passive"))
      (node (ref "C8") (pin "2") (pinfunction "2_2") (pintype "passive"))
      (node (ref "C80") (pin "2") (pinfunction "2_2") (pintype "passive"))
      (node (ref "C81") (pin "2") (pinfunction "2_2") (pintype "passive"))
      (node (ref "C82") (pin "2") (pinfunction "2_2") (pintype "passive"))
      (node (ref "C83") (pin "2") (pinfunction "2_2") (pintype "passive"))
      (node (ref "C84") (pin "2") (pinfunction "2_2") (pintype "passive"))
      (node (ref "C85") (pin "2") (pinfunction "2_2") (pintype "passive"))
      (node (ref "C86") (pin "2") (pinfunction "2_2") (pintype "passive"))
      (node (ref "C87") (pin "2") (pinfunction "2_2") (pintype "passive"))
      (node (ref "C88") (pin "2") (pinfunction "2_2") (pintype "passive"))
      (node (ref "C89") (pin "2") (pinfunction "2_2") (pintype "passive"))
      (node (ref "C9") (pin "2") (pinfunction "2_2") (pintype "passive"))
      (node (ref "C90") (pin "2") (pinfunction "2_2") (pintype "passive"))
      (node (ref "C91") (pin "1") (pinfunction "1_1") (pintype "passive"))
      (node (ref "C92") (pin "2") (pinfunction "2_2") (pintype "passive"))
      (node (ref "C93") (pin "2") (pinfunction "2_2") (pintype "passive"))
      (node (ref "GND") (pin "TP") (pinfunction "TP_TP") (pintype "input"))
      (node (ref "GND75") (pin "TP") (pinfunction "TP_TP") (pintype "input"))
      (node (ref "GND77") (pin "TP") (pinfunction "TP_TP") (pintype "input"))
      (node (ref "R12") (pin "2") (pinfunction "2_2") (pintype "passive"))
      (node (ref "R15") (pin "2") (pinfunction "2_2") (pintype "passive"))
      (node (ref "R18") (pin "2") (pinfunction "2_2") (pintype "passive"))
      (node (ref "R22") (pin "1") (pinfunction "1_1") (pintype "passive"))
      (node (ref "R2X") (pin "2") (pinfunction "2_2") (pintype "passive"))
      (node (ref "R3") (pin "2") (pinfunction "2_2") (pintype "passive"))
      (node (ref "R6") (pin "2") (pinfunction "2_2") (pintype "passive"))
      (node (ref "R9") (pin "2") (pinfunction "2_2") (pintype "passive"))
      (node (ref "SENSOR") (pin "A21") (pinfunction "GND_A21") (pintype "power_in"))
      (node (ref "SENSOR") (pin "A25") (pinfunction "GND_A25") (pintype "power_in"))
      (node (ref "SENSOR") (pin "A28") (pinfunction "GND_A28") (pintype "power_in"))
      (node (ref "SENSOR") (pin "A29") (pinfunction "GND_A29") (pintype "power_in"))
      (node (ref "SENSOR") (pin "A9") (pinfunction "GND_A9") (pintype "power_in"))
      (node (ref "SENSOR") (pin "B22") (pinfunction "GND_B22") (pintype "power_in"))
      (node (ref "SENSOR") (pin "B26") (pinfunction "GND_B26") (pintype "power_in"))
      (node (ref "SENSOR") (pin "B27") (pinfunction "GND_B27") (pintype "power_in"))
      (node (ref "SENSOR") (pin "B28") (pinfunction "GND_B28") (pintype "power_in"))
      (node (ref "SENSOR") (pin "B5") (pinfunction "GND_B5") (pintype "power_in"))
      (node (ref "SENSOR") (pin "C15") (pinfunction "GND_C15") (pintype "power_in"))
      (node (ref "SENSOR") (pin "C16") (pinfunction "GND_C16") (pintype "power_in"))
      (node (ref "SENSOR") (pin "C28") (pinfunction "GND_C28") (pintype "power_in"))
      (node (ref "SENSOR") (pin "D2") (pinfunction "GND_D2") (pintype "power_in"))
      (node (ref "SENSOR") (pin "D25") (pinfunction "GND_D25") (pintype "power_in"))
      (node (ref "SENSOR") (pin "D27") (pinfunction "GND_D27") (pintype "power_in"))
      (node (ref "SENSOR") (pin "D29") (pinfunction "GND_D29") (pintype "power_in"))
      (node (ref "SENSOR") (pin "E15") (pinfunction "GND_E15") (pintype "power_in"))
      (node (ref "SENSOR") (pin "E16") (pinfunction "GND_E16") (pintype "power_in"))
      (node (ref "SENSOR") (pin "E25") (pinfunction "GND_E25") (pintype "power_in"))
      (node (ref "SENSOR") (pin "E27") (pinfunction "GND_E27") (pintype "power_in"))
      (node (ref "SENSOR") (pin "E3") (pinfunction "GND_E3") (pintype "power_in"))
      (node (ref "SENSOR") (pin "E4") (pinfunction "DIO2_E4") (pintype "output"))
      (node (ref "SENSOR") (pin "F27") (pinfunction "GND_F27") (pintype "power_in"))
      (node (ref "SENSOR") (pin "F4") (pinfunction "DIO1_F4") (pintype "output"))
      (node (ref "SENSOR") (pin "G3") (pinfunction "DIO4_G3") (pintype "output"))
      (node (ref "SENSOR") (pin "G5") (pinfunction "GND_G5") (pintype "power_in"))
      (node (ref "SENSOR") (pin "H1") (pinfunction "GND_H1") (pintype "power_in"))
      (node (ref "SENSOR") (pin "H21") (pinfunction "GND_H21") (pintype "power_in"))
      (node (ref "SENSOR") (pin "H25") (pinfunction "GND_H25") (pintype "power_in"))
      (node (ref "SENSOR") (pin "H27") (pinfunction "GND_H27") (pintype "power_in"))
      (node (ref "SENSOR") (pin "H4") (pinfunction "DIO3_H4") (pintype "output"))
      (node (ref "SENSOR") (pin "H6") (pinfunction "GND_H6") (pintype "power_in"))
      (node (ref "SENSOR") (pin "H9") (pinfunction "GND_H9") (pintype "power_in"))
      (node (ref "U1") (pin "6") (pinfunction "ANODE_6") (pintype "input"))
      (node (ref "U2") (pin "6") (pinfunction "ANODE_6") (pintype "input"))
      (node (ref "U3") (pin "2") (pinfunction "GND_2") (pintype "power_in"))
      (node (ref "U3") (pin "EP") (pinfunction "EP_EP") (pintype "power_in"))
      (node (ref "U4") (pin "16") (pinfunction "DIR2_16") (pintype "input"))
      (node (ref "U4") (pin "7") (pinfunction "~{OE}_7") (pintype "input"))
      (node (ref "U4") (pin "8") (pinfunction "GND_8") (pintype "passive"))
      (node (ref "U5") (pin "6") (pinfunction "DIR4_6") (pintype "input"))
      (node (ref "U5") (pin "7") (pinfunction "~{OE}_7") (pintype "input"))
      (node (ref "U5") (pin "8") (pinfunction "GND_8") (pintype "passive"))
      (node (ref "U6") (pin "16") (pinfunction "DIR2_16") (pintype "input"))
      (node (ref "U6") (pin "7") (pinfunction "~{OE}_7") (pintype "input"))
      (node (ref "U6") (pin "8") (pinfunction "GND_8") (pintype "passive"))
      (node (ref "U7") (pin "4") (pinfunction "GND_4") (pintype "power_in"))
      (node (ref "U7") (pin "5") (pinfunction "A2_5") (pintype "input"))
      (node (ref "U7") (pin "6") (pinfunction "A1_6") (pintype "input"))
      (node (ref "U7") (pin "7") (pinfunction "A0_7") (pintype "input"))
      (node (ref "UEP") (pin "1") (pinfunction "A0_1") (pintype "input"))
      (node (ref "UEP") (pin "2") (pinfunction "A1_2") (pintype "input"))
      (node (ref "UEP") (pin "3") (pinfunction "A2_3") (pintype "input"))
      (node (ref "UEP") (pin "4") (pinfunction "GND_4") (pintype "passive"))
      (node (ref "UEP") (pin "EP") (pinfunction "EP_EP") (pintype "passive"))
      (node (ref "UNE") (pin "4") (pinfunction "VSS_4") (pintype "power_in"))
      (node (ref "UNE") (pin "EP") (pinfunction "EP_EP") (pintype "passive"))
      (node (ref "UNN") (pin "4") (pinfunction "VSS_4") (pintype "power_in"))
      (node (ref "UNN") (pin "EP") (pinfunction "EP_EP") (pintype "passive"))
      (node (ref "UNW") (pin "4") (pinfunction "VSS_4") (pintype "power_in"))
      (node (ref "UNW") (pin "EP") (pinfunction "EP_EP") (pintype "passive"))
      (node (ref "USE") (pin "4") (pinfunction "VSS_4") (pintype "power_in"))
      (node (ref "USE") (pin "EP") (pinfunction "EP_EP") (pintype "passive"))
      (node (ref "USS") (pin "4") (pinfunction "VSS_4") (pintype "power_in"))
      (node (ref "USS") (pin "EP") (pinfunction "EP_EP") (pintype "passive"))
      (node (ref "USW") (pin "4") (pinfunction "VSS_4") (pintype "power_in"))
      (node (ref "USW") (pin "EP") (pinfunction "EP_EP") (pintype "passive"))
      (node (ref "X-NORTH") (pin "102") (pinfunction "102_102") (pintype "bidirectional"))
      (node (ref "X-NORTH") (pin "103") (pinfunction "103_103") (pintype "bidirectional"))
      (node (ref "X-NORTH") (pin "108") (pinfunction "108_108") (pintype "bidirectional"))
      (node (ref "X-NORTH") (pin "114") (pinfunction "114_114") (pintype "bidirectional"))
      (node (ref "X-NORTH") (pin "12") (pinfunction "12_12") (pintype "bidirectional"))
      (node (ref "X-NORTH") (pin "120") (pinfunction "120_120") (pintype "bidirectional"))
      (node (ref "X-NORTH") (pin "126") (pinfunction "126_126") (pintype "bidirectional"))
      (node (ref "X-NORTH") (pin "132") (pinfunction "132_132") (pintype "bidirectional"))
      (node (ref "X-NORTH") (pin "138") (pinfunction "138_138") (pintype "bidirectional"))
      (node (ref "X-NORTH") (pin "139") (pinfunction "139_139") (pintype "bidirectional"))
      (node (ref "X-NORTH") (pin "18") (pinfunction "18_18") (pintype "bidirectional"))
      (node (ref "X-NORTH") (pin "24") (pinfunction "24_24") (pintype "bidirectional"))
      (node (ref "X-NORTH") (pin "30") (pinfunction "30_30") (pintype "bidirectional"))
      (node (ref "X-NORTH") (pin "36") (pinfunction "36_36") (pintype "bidirectional"))
      (node (ref "X-NORTH") (pin "42") (pinfunction "42_42") (pintype "bidirectional"))
      (node (ref "X-NORTH") (pin "43") (pinfunction "43_43") (pintype "bidirectional"))
      (node (ref "X-NORTH") (pin "48") (pinfunction "48_48") (pintype "bidirectional"))
      (node (ref "X-NORTH") (pin "54") (pinfunction "54_54") (pintype "bidirectional"))
      (node (ref "X-NORTH") (pin "60") (pinfunction "60_60") (pintype "bidirectional"))
      (node (ref "X-NORTH") (pin "66") (pinfunction "66_66") (pintype "bidirectional"))
      (node (ref "X-NORTH") (pin "72") (pinfunction "72_72") (pintype "bidirectional"))
      (node (ref "X-NORTH") (pin "78") (pinfunction "78_78") (pintype "bidirectional"))
      (node (ref "X-NORTH") (pin "84") (pinfunction "84_84") (pintype "bidirectional"))
      (node (ref "X-NORTH") (pin "90") (pinfunction "90_90") (pintype "bidirectional"))
      (node (ref "X-NORTH") (pin "96") (pinfunction "96_96") (pintype "bidirectional"))
      (node (ref "X-SOUTH") (pin "102") (pinfunction "102_102") (pintype "bidirectional"))
      (node (ref "X-SOUTH") (pin "103") (pinfunction "103_103") (pintype "bidirectional"))
      (node (ref "X-SOUTH") (pin "108") (pinfunction "108_108") (pintype "bidirectional"))
      (node (ref "X-SOUTH") (pin "114") (pinfunction "114_114") (pintype "bidirectional"))
      (node (ref "X-SOUTH") (pin "12") (pinfunction "12_12") (pintype "bidirectional"))
      (node (ref "X-SOUTH") (pin "120") (pinfunction "120_120") (pintype "bidirectional"))
      (node (ref "X-SOUTH") (pin "126") (pinfunction "126_126") (pintype "bidirectional"))
      (node (ref "X-SOUTH") (pin "132") (pinfunction "132_132") (pintype "bidirectional"))
      (node (ref "X-SOUTH") (pin "138") (pinfunction "138_138") (pintype "bidirectional"))
      (node (ref "X-SOUTH") (pin "139") (pinfunction "139_139") (pintype "bidirectional"))
      (node (ref "X-SOUTH") (pin "18") (pinfunction "18_18") (pintype "bidirectional"))
      (node (ref "X-SOUTH") (pin "24") (pinfunction "24_24") (pintype "bidirectional"))
      (node (ref "X-SOUTH") (pin "30") (pinfunction "30_30") (pintype "bidirectional"))
      (node (ref "X-SOUTH") (pin "36") (pinfunction "36_36") (pintype "bidirectional"))
      (node (ref "X-SOUTH") (pin "42") (pinfunction "42_42") (pintype "bidirectional"))
      (node (ref "X-SOUTH") (pin "43") (pinfunction "43_43") (pintype "bidirectional"))
      (node (ref "X-SOUTH") (pin "48") (pinfunction "48_48") (pintype "bidirectional"))
      (node (ref "X-SOUTH") (pin "54") (pinfunction "54_54") (pintype "bidirectional"))
      (node (ref "X-SOUTH") (pin "60") (pinfunction "60_60") (pintype "bidirectional"))
      (node (ref "X-SOUTH") (pin "66") (pinfunction "66_66") (pintype "bidirectional"))
      (node (ref "X-SOUTH") (pin "72") (pinfunction "72_72") (pintype "bidirectional"))
      (node (ref "X-SOUTH") (pin "78") (pinfunction "78_78") (pintype "bidirectional"))
      (node (ref "X-SOUTH") (pin "84") (pinfunction "84_84") (pintype "bidirectional"))
      (node (ref "X-SOUTH") (pin "90") (pinfunction "90_90") (pintype "bidirectional"))
      (node (ref "X-SOUTH") (pin "96") (pinfunction "96_96") (pintype "bidirectional"))
    )
    (net (code "4") (name "N$42") (class "Default")
      (node (ref "SENSOR") (pin "A2") (pinfunction "TANA_A2") (pintype "output"))
    )
    (net (code "5") (name "N00_N") (class "Default")
      (node (ref "R25") (pin "2") (pinfunction "2_2") (pintype "passive"))
      (node (ref "SENSOR") (pin "E6") (pinfunction "LVDS_CLK_P_E6") (pintype "input"))
      (node (ref "X-NORTH") (pin "16") (pinfunction "16_16") (pintype "bidirectional"))
    )
    (net (code "6") (name "N00_P") (class "Default")
      (node (ref "R25") (pin "1") (pinfunction "1_1") (pintype "passive"))
      (node (ref "SENSOR") (pin "E5") (pinfunction "LVDS_CLK_N_E5") (pintype "input"))
      (node (ref "X-NORTH") (pin "14") (pinfunction "14_14") (pintype "bidirectional"))
    )
    (net (code "7") (name "N01_N") (class "Default")
      (node (ref "SENSOR") (pin "G7") (pinfunction "OUTCLK_P_G7") (pintype "output"))
      (node (ref "X-NORTH") (pin "17") (pinfunction "17_17") (pintype "bidirectional"))
    )
    (net (code "8") (name "N01_P") (class "Default")
      (node (ref "SENSOR") (pin "G6") (pinfunction "OUTCLK_N_G6") (pintype "output"))
      (node (ref "X-NORTH") (pin "15") (pinfunction "15_15") (pintype "bidirectional"))
    )
    (net (code "9") (name "N02_N") (class "Default")
      (node (ref "SENSOR") (pin "F7") (pinfunction "OUT33_P_F7") (pintype "output"))
      (node (ref "X-NORTH") (pin "22") (pinfunction "22_22") (pintype "bidirectional"))
    )
    (net (code "10") (name "N02_P") (class "Default")
      (node (ref "SENSOR") (pin "F6") (pinfunction "OUT33_N_F6") (pintype "output"))
      (node (ref "X-NORTH") (pin "20") (pinfunction "20_20") (pintype "bidirectional"))
    )
    (net (code "11") (name "N03_N") (class "Default")
      (node (ref "X-NORTH") (pin "23") (pinfunction "23_23") (pintype "bidirectional"))
    )
    (net (code "12") (name "N03_P") (class "Default")
      (node (ref "X-NORTH") (pin "21") (pinfunction "21_21") (pintype "bidirectional"))
    )
    (net (code "13") (name "N04_N") (class "Default")
      (node (ref "SENSOR") (pin "E8") (pinfunction "OUT35_P_E8") (pintype "output"))
      (node (ref "X-NORTH") (pin "28") (pinfunction "28_28") (pintype "bidirectional"))
    )
    (net (code "14") (name "N04_P") (class "Default")
      (node (ref "SENSOR") (pin "E7") (pinfunction "OUT35_N_E7") (pintype "output"))
      (node (ref "X-NORTH") (pin "26") (pinfunction "26_26") (pintype "bidirectional"))
    )
    (net (code "15") (name "N05_N") (class "Default")
      (node (ref "SENSOR") (pin "H8") (pinfunction "OUT34_P_H8") (pintype "output"))
      (node (ref "X-NORTH") (pin "29") (pinfunction "29_29") (pintype "bidirectional"))
    )
    (net (code "16") (name "N05_P") (class "Default")
      (node (ref "SENSOR") (pin "H7") (pinfunction "OUT34_N_H7") (pintype "output"))
      (node (ref "X-NORTH") (pin "27") (pinfunction "27_27") (pintype "bidirectional"))
    )
    (net (code "17") (name "N06_N") (class "Default")
      (node (ref "SENSOR") (pin "F9") (pinfunction "OUT37_P_F9") (pintype "output"))
      (node (ref "X-NORTH") (pin "34") (pinfunction "34_34") (pintype "bidirectional"))
    )
    (net (code "18") (name "N06_P") (class "Default")
      (node (ref "SENSOR") (pin "F8") (pinfunction "OUT37_N_F8") (pintype "output"))
      (node (ref "X-NORTH") (pin "32") (pinfunction "32_32") (pintype "bidirectional"))
    )
    (net (code "19") (name "N07_N") (class "Default")
      (node (ref "SENSOR") (pin "G9") (pinfunction "OUT36_P_G9") (pintype "output"))
      (node (ref "X-NORTH") (pin "35") (pinfunction "35_35") (pintype "bidirectional"))
    )
    (net (code "20") (name "N07_P") (class "Default")
      (node (ref "SENSOR") (pin "G8") (pinfunction "OUT36_N_G8") (pintype "output"))
      (node (ref "X-NORTH") (pin "33") (pinfunction "33_33") (pintype "bidirectional"))
    )
    (net (code "21") (name "N08_N") (class "Default")
      (node (ref "SENSOR") (pin "E10") (pinfunction "OUT38_P_E10") (pintype "output"))
      (node (ref "X-NORTH") (pin "40") (pinfunction "40_40") (pintype "bidirectional"))
    )
    (net (code "22") (name "N08_P") (class "Default")
      (node (ref "SENSOR") (pin "E9") (pinfunction "OUT38_N_E9") (pintype "output"))
      (node (ref "X-NORTH") (pin "38") (pinfunction "38_38") (pintype "bidirectional"))
    )
    (net (code "23") (name "N09_N") (class "Default")
      (node (ref "SENSOR") (pin "G11") (pinfunction "OUT39_P_G11") (pintype "output"))
      (node (ref "X-NORTH") (pin "41") (pinfunction "41_41") (pintype "bidirectional"))
    )
    (net (code "24") (name "N09_P") (class "Default")
      (node (ref "SENSOR") (pin "G10") (pinfunction "OUT39_N_G10") (pintype "output"))
      (node (ref "X-NORTH") (pin "39") (pinfunction "39_39") (pintype "bidirectional"))
    )
    (net (code "25") (name "N10_N") (class "Default")
      (node (ref "SENSOR") (pin "F11") (pinfunction "OUT40_P_F11") (pintype "output"))
      (node (ref "X-NORTH") (pin "46") (pinfunction "46_46") (pintype "bidirectional"))
    )
    (net (code "26") (name "N10_P") (class "Default")
      (node (ref "SENSOR") (pin "F10") (pinfunction "OUT40_N_F10") (pintype "output"))
      (node (ref "X-NORTH") (pin "44") (pinfunction "44_44") (pintype "bidirectional"))
    )
    (net (code "27") (name "N11_N") (class "Default")
      (node (ref "SENSOR") (pin "H12") (pinfunction "OUT41_P_H12") (pintype "output"))
      (node (ref "X-NORTH") (pin "47") (pinfunction "47_47") (pintype "bidirectional"))
    )
    (net (code "28") (name "N11_P") (class "Default")
      (node (ref "SENSOR") (pin "H11") (pinfunction "OUT41_N_H11") (pintype "output"))
      (node (ref "X-NORTH") (pin "45") (pinfunction "45_45") (pintype "bidirectional"))
    )
    (net (code "29") (name "N12_N") (class "Default")
      (node (ref "SENSOR") (pin "E12") (pinfunction "OUT42_P_E12") (pintype "output"))
      (node (ref "X-NORTH") (pin "52") (pinfunction "52_52") (pintype "bidirectional"))
    )
    (net (code "30") (name "N12_P") (class "Default")
      (node (ref "SENSOR") (pin "E11") (pinfunction "OUT42_N_E11") (pintype "output"))
      (node (ref "X-NORTH") (pin "50") (pinfunction "50_50") (pintype "bidirectional"))
    )
    (net (code "31") (name "N13_N") (class "Default")
      (node (ref "SENSOR") (pin "G13") (pinfunction "OUT43_P_G13") (pintype "output"))
      (node (ref "X-NORTH") (pin "53") (pinfunction "53_53") (pintype "bidirectional"))
    )
    (net (code "32") (name "N13_P") (class "Default")
      (node (ref "SENSOR") (pin "G12") (pinfunction "OUT43_N_G12") (pintype "output"))
      (node (ref "X-NORTH") (pin "51") (pinfunction "51_51") (pintype "bidirectional"))
    )
    (net (code "33") (name "N14_N") (class "Default")
      (node (ref "SENSOR") (pin "F13") (pinfunction "OUT44_P_F13") (pintype "output"))
      (node (ref "X-NORTH") (pin "58") (pinfunction "58_58") (pintype "bidirectional"))
    )
    (net (code "34") (name "N14_P") (class "Default")
      (node (ref "SENSOR") (pin "F12") (pinfunction "OUT44_N_F12") (pintype "output"))
      (node (ref "X-NORTH") (pin "56") (pinfunction "56_56") (pintype "bidirectional"))
    )
    (net (code "35") (name "N15_N") (class "Default")
      (node (ref "SENSOR") (pin "H14") (pinfunction "OUT45_P_H14") (pintype "output"))
      (node (ref "X-NORTH") (pin "59") (pinfunction "59_59") (pintype "bidirectional"))
    )
    (net (code "36") (name "N15_P") (class "Default")
      (node (ref "SENSOR") (pin "H13") (pinfunction "OUT45_N_H13") (pintype "output"))
      (node (ref "X-NORTH") (pin "57") (pinfunction "57_57") (pintype "bidirectional"))
    )
    (net (code "37") (name "N16_N") (class "Default")
      (node (ref "SENSOR") (pin "E14") (pinfunction "OUT46_P_E14") (pintype "output"))
      (node (ref "X-NORTH") (pin "64") (pinfunction "64_64") (pintype "bidirectional"))
    )
    (net (code "38") (name "N16_P") (class "Default")
      (node (ref "SENSOR") (pin "E13") (pinfunction "OUT46_N_E13") (pintype "output"))
      (node (ref "X-NORTH") (pin "62") (pinfunction "62_62") (pintype "bidirectional"))
    )
    (net (code "39") (name "N17_N") (class "Default")
      (node (ref "SENSOR") (pin "G15") (pinfunction "OUT47_P_G15") (pintype "output"))
      (node (ref "X-NORTH") (pin "65") (pinfunction "65_65") (pintype "bidirectional"))
    )
    (net (code "40") (name "N17_P") (class "Default")
      (node (ref "SENSOR") (pin "G14") (pinfunction "OUT47_N_G14") (pintype "output"))
      (node (ref "X-NORTH") (pin "63") (pinfunction "63_63") (pintype "bidirectional"))
    )
    (net (code "41") (name "N18_N") (class "Default")
      (node (ref "SENSOR") (pin "F15") (pinfunction "OUT48_P_F15") (pintype "output"))
      (node (ref "X-NORTH") (pin "70") (pinfunction "70_70") (pintype "bidirectional"))
    )
    (net (code "42") (name "N18_P") (class "Default")
      (node (ref "SENSOR") (pin "F14") (pinfunction "OUT48_N_F14") (pintype "output"))
      (node (ref "X-NORTH") (pin "68") (pinfunction "68_68") (pintype "bidirectional"))
    )
    (net (code "43") (name "N19_N") (class "Default")
      (node (ref "SENSOR") (pin "G17") (pinfunction "OUT50_P_G17") (pintype "output"))
      (node (ref "X-NORTH") (pin "71") (pinfunction "71_71") (pintype "bidirectional"))
    )
    (net (code "44") (name "N19_P") (class "Default")
      (node (ref "SENSOR") (pin "G16") (pinfunction "OUT50_N_G16") (pintype "output"))
      (node (ref "X-NORTH") (pin "69") (pinfunction "69_69") (pintype "bidirectional"))
    )
    (net (code "45") (name "N20_N") (class "Default")
      (node (ref "SENSOR") (pin "F17") (pinfunction "OUT49_P_F17") (pintype "output"))
      (node (ref "X-NORTH") (pin "76") (pinfunction "76_76") (pintype "bidirectional"))
    )
    (net (code "46") (name "N20_P") (class "Default")
      (node (ref "SENSOR") (pin "F16") (pinfunction "OUT49_N_F16") (pintype "output"))
      (node (ref "X-NORTH") (pin "74") (pinfunction "74_74") (pintype "bidirectional"))
    )
    (net (code "47") (name "N21_N") (class "Default")
      (node (ref "SENSOR") (pin "H18") (pinfunction "OUT52_P_H18") (pintype "output"))
      (node (ref "X-NORTH") (pin "77") (pinfunction "77_77") (pintype "bidirectional"))
    )
    (net (code "48") (name "N21_P") (class "Default")
      (node (ref "SENSOR") (pin "H17") (pinfunction "OUT52_N_H17") (pintype "output"))
      (node (ref "X-NORTH") (pin "75") (pinfunction "75_75") (pintype "bidirectional"))
    )
    (net (code "49") (name "N22_N") (class "Default")
      (node (ref "SENSOR") (pin "E18") (pinfunction "OUT51_P_E18") (pintype "output"))
      (node (ref "X-NORTH") (pin "82") (pinfunction "82_82") (pintype "bidirectional"))
    )
    (net (code "50") (name "N22_P") (class "Default")
      (node (ref "SENSOR") (pin "E17") (pinfunction "OUT51_N_E17") (pintype "output"))
      (node (ref "X-NORTH") (pin "80") (pinfunction "80_80") (pintype "bidirectional"))
    )
    (net (code "51") (name "N23_N") (class "Default")
      (node (ref "SENSOR") (pin "G19") (pinfunction "OUT54_P_G19") (pintype "output"))
      (node (ref "X-NORTH") (pin "83") (pinfunction "83_83") (pintype "bidirectional"))
    )
    (net (code "52") (name "N23_P") (class "Default")
      (node (ref "SENSOR") (pin "G18") (pinfunction "OUT54_N_G18") (pintype "output"))
      (node (ref "X-NORTH") (pin "81") (pinfunction "81_81") (pintype "bidirectional"))
    )
    (net (code "53") (name "N24_N") (class "Default")
      (node (ref "SENSOR") (pin "F19") (pinfunction "OUT53_P_F19") (pintype "output"))
      (node (ref "X-NORTH") (pin "88") (pinfunction "88_88") (pintype "bidirectional"))
    )
    (net (code "54") (name "N24_P") (class "Default")
      (node (ref "SENSOR") (pin "F18") (pinfunction "OUT53_N_F18") (pintype "output"))
      (node (ref "X-NORTH") (pin "86") (pinfunction "86_86") (pintype "bidirectional"))
    )
    (net (code "55") (name "N25_N") (class "Default")
      (node (ref "SENSOR") (pin "H20") (pinfunction "OUT56_P_H20") (pintype "output"))
      (node (ref "X-NORTH") (pin "89") (pinfunction "89_89") (pintype "bidirectional"))
    )
    (net (code "56") (name "N25_P") (class "Default")
      (node (ref "SENSOR") (pin "H19") (pinfunction "OUT56_N_H19") (pintype "output"))
      (node (ref "X-NORTH") (pin "87") (pinfunction "87_87") (pintype "bidirectional"))
    )
    (net (code "57") (name "N26_N") (class "Default")
      (node (ref "SENSOR") (pin "E20") (pinfunction "OUT55_P_E20") (pintype "output"))
      (node (ref "X-NORTH") (pin "94") (pinfunction "94_94") (pintype "bidirectional"))
    )
    (net (code "58") (name "N26_P") (class "Default")
      (node (ref "SENSOR") (pin "E19") (pinfunction "OUT55_N_E19") (pintype "output"))
      (node (ref "X-NORTH") (pin "92") (pinfunction "92_92") (pintype "bidirectional"))
    )
    (net (code "59") (name "N27_N") (class "Default")
      (node (ref "SENSOR") (pin "G21") (pinfunction "OUT58_P_G21") (pintype "output"))
      (node (ref "X-NORTH") (pin "95") (pinfunction "95_95") (pintype "bidirectional"))
    )
    (net (code "60") (name "N27_P") (class "Default")
      (node (ref "SENSOR") (pin "G20") (pinfunction "OUT58_N_G20") (pintype "output"))
      (node (ref "X-NORTH") (pin "93") (pinfunction "93_93") (pintype "bidirectional"))
    )
    (net (code "61") (name "N28_N") (class "Default")
      (node (ref "SENSOR") (pin "F21") (pinfunction "OUT57_P_F21") (pintype "output"))
      (node (ref "X-NORTH") (pin "100") (pinfunction "100_100") (pintype "bidirectional"))
    )
    (net (code "62") (name "N28_P") (class "Default")
      (node (ref "SENSOR") (pin "F20") (pinfunction "OUT57_N_F20") (pintype "output"))
      (node (ref "X-NORTH") (pin "98") (pinfunction "98_98") (pintype "bidirectional"))
    )
    (net (code "63") (name "N29_N") (class "Default")
      (node (ref "SENSOR") (pin "G23") (pinfunction "OUT61_P_G23") (pintype "output"))
      (node (ref "X-NORTH") (pin "101") (pinfunction "101_101") (pintype "bidirectional"))
    )
    (net (code "64") (name "N29_P") (class "Default")
      (node (ref "SENSOR") (pin "G22") (pinfunction "OUT61_N_G22") (pintype "output"))
      (node (ref "X-NORTH") (pin "99") (pinfunction "99_99") (pintype "bidirectional"))
    )
    (net (code "65") (name "N30_N") (class "Default")
      (node (ref "SENSOR") (pin "E22") (pinfunction "OUT59_P_E22") (pintype "output"))
      (node (ref "X-NORTH") (pin "106") (pinfunction "106_106") (pintype "bidirectional"))
    )
    (net (code "66") (name "N30_P") (class "Default")
      (node (ref "SENSOR") (pin "E21") (pinfunction "OUT59_N_E21") (pintype "output"))
      (node (ref "X-NORTH") (pin "104") (pinfunction "104_104") (pintype "bidirectional"))
    )
    (net (code "67") (name "N31_N") (class "Default")
      (node (ref "SENSOR") (pin "H24") (pinfunction "OUT63_P_H24") (pintype "output"))
      (node (ref "X-NORTH") (pin "107") (pinfunction "107_107") (pintype "bidirectional"))
    )
    (net (code "68") (name "N31_P") (class "Default")
      (node (ref "SENSOR") (pin "H23") (pinfunction "OUT63_N_H23") (pintype "output"))
      (node (ref "X-NORTH") (pin "105") (pinfunction "105_105") (pintype "bidirectional"))
    )
    (net (code "69") (name "N32_N") (class "Default")
      (node (ref "SENSOR") (pin "F23") (pinfunction "OUT60_P_F23") (pintype "output"))
      (node (ref "X-NORTH") (pin "112") (pinfunction "112_112") (pintype "bidirectional"))
    )
    (net (code "70") (name "N32_P") (class "Default")
      (node (ref "SENSOR") (pin "F22") (pinfunction "OUT60_N_F22") (pintype "output"))
      (node (ref "X-NORTH") (pin "110") (pinfunction "110_110") (pintype "bidirectional"))
    )
    (net (code "71") (name "N33_N") (class "Default")
      (node (ref "SENSOR") (pin "G25") (pinfunction "OUT64_P_G25") (pintype "output"))
      (node (ref "X-NORTH") (pin "113") (pinfunction "113_113") (pintype "bidirectional"))
    )
    (net (code "72") (name "N33_P") (class "Default")
      (node (ref "SENSOR") (pin "G24") (pinfunction "OUT64_N_G24") (pintype "output"))
      (node (ref "X-NORTH") (pin "111") (pinfunction "111_111") (pintype "bidirectional"))
    )
    (net (code "73") (name "N34_N") (class "Default")
      (node (ref "SENSOR") (pin "E24") (pinfunction "OUT62_P_E24") (pintype "output"))
      (node (ref "X-NORTH") (pin "118") (pinfunction "118_118") (pintype "bidirectional"))
    )
    (net (code "74") (name "N34_P") (class "Default")
      (node (ref "SENSOR") (pin "E23") (pinfunction "OUT62_N_E23") (pintype "output"))
      (node (ref "X-NORTH") (pin "116") (pinfunction "116_116") (pintype "bidirectional"))
    )
    (net (code "75") (name "N35_N") (class "Default")
      (node (ref "U6") (pin "4") (pinfunction "A4_4") (pintype "bidirectional"))
      (node (ref "X-NORTH") (pin "119") (pinfunction "119_119") (pintype "bidirectional"))
    )
    (net (code "76") (name "N35_P") (class "Default")
      (node (ref "U6") (pin "3") (pinfunction "A3_3") (pintype "bidirectional"))
      (node (ref "X-NORTH") (pin "117") (pinfunction "117_117") (pintype "bidirectional"))
    )
    (net (code "77") (name "N36_N") (class "Default")
      (node (ref "X-NORTH") (pin "124") (pinfunction "124_124") (pintype "bidirectional"))
    )
    (net (code "78") (name "N36_P") (class "Default")
      (node (ref "X-NORTH") (pin "122") (pinfunction "122_122") (pintype "bidirectional"))
    )
    (net (code "79") (name "N37_N") (class "Default")
      (node (ref "U5") (pin "3") (pinfunction "A3_3") (pintype "bidirectional"))
      (node (ref "X-NORTH") (pin "125") (pinfunction "125_125") (pintype "bidirectional"))
    )
    (net (code "80") (name "N37_P") (class "Default")
      (node (ref "U5") (pin "4") (pinfunction "A4_4") (pintype "bidirectional"))
      (node (ref "X-NORTH") (pin "123") (pinfunction "123_123") (pintype "bidirectional"))
    )
    (net (code "81") (name "N38_N") (class "Default")
      (node (ref "U6") (pin "2") (pinfunction "A2_2") (pintype "bidirectional"))
      (node (ref "X-NORTH") (pin "130") (pinfunction "130_130") (pintype "bidirectional"))
    )
    (net (code "82") (name "N38_P") (class "Default")
      (node (ref "U6") (pin "1") (pinfunction "A1_1") (pintype "bidirectional"))
      (node (ref "X-NORTH") (pin "128") (pinfunction "128_128") (pintype "bidirectional"))
    )
    (net (code "83") (name "N39_N") (class "Default")
      (node (ref "U5") (pin "1") (pinfunction "A1_1") (pintype "bidirectional"))
      (node (ref "X-NORTH") (pin "131") (pinfunction "131_131") (pintype "bidirectional"))
    )
    (net (code "84") (name "N39_P") (class "Default")
      (node (ref "U5") (pin "2") (pinfunction "A2_2") (pintype "bidirectional"))
      (node (ref "X-NORTH") (pin "129") (pinfunction "129_129") (pintype "bidirectional"))
    )
    (net (code "85") (name "N_CHK_EN") (class "Default")
      (node (ref "X-NORTH") (pin "8") (pinfunction "8_8") (pintype "bidirectional"))
    )
    (net (code "86") (name "N_CHK_V") (class "Default")
      (node (ref "C2") (pin "1") (pinfunction "1_1") (pintype "passive"))
      (node (ref "C3") (pin "1") (pinfunction "1_1") (pintype "passive"))
      (node (ref "C4") (pin "1") (pinfunction "1_1") (pintype "passive"))
      (node (ref "R19") (pin "1") (pinfunction "1_1") (pintype "passive"))
      (node (ref "TP1") (pin "TP") (pinfunction "TP_TP") (pintype "input"))
      (node (ref "UNE") (pin "8") (pinfunction "VDD_8") (pintype "power_in"))
      (node (ref "UNN") (pin "8") (pinfunction "VDD_8") (pintype "power_in"))
      (node (ref "UNW") (pin "8") (pinfunction "VDD_8") (pintype "power_in"))
      (node (ref "X-NORTH") (pin "10") (pinfunction "10_10") (pintype "bidirectional"))
    )
    (net (code "87") (name "N_I2C_EN") (class "Default")
      (node (ref "X-NORTH") (pin "137") (pinfunction "137_137") (pintype "bidirectional"))
    )
    (net (code "88") (name "N_I2C_V") (class "Default")
      (node (ref "C1") (pin "1") (pinfunction "1_1") (pintype "passive"))
      (node (ref "R1X") (pin "1") (pinfunction "1_1") (pintype "passive"))
      (node (ref "UEP") (pin "8") (pinfunction "VCC_8") (pintype "power_in"))
      (node (ref "X-NORTH") (pin "135") (pinfunction "135_135") (pintype "bidirectional"))
    )
    (net (code "89") (name "N_REF") (class "Default")
      (node (ref "R19") (pin "2") (pinfunction "2_2") (pintype "passive"))
      (node (ref "TP2") (pin "TP") (pinfunction "TP_TP") (pintype "input"))
      (node (ref "U1") (pin "1") (pinfunction "CATHODE_1") (pintype "output"))
      (node (ref "U1") (pin "3") (pinfunction "REF_3") (pintype "input"))
      (node (ref "UNE") (pin "2") (pinfunction "VINA-_2") (pintype "input"))
      (node (ref "UNE") (pin "5") (pinfunction "VINB+_5") (pintype "input"))
      (node (ref "UNN") (pin "2") (pinfunction "VINA-_2") (pintype "input"))
      (node (ref "UNN") (pin "5") (pinfunction "VINB+_5") (pintype "input"))
      (node (ref "UNW") (pin "2") (pinfunction "VINA-_2") (pintype "input"))
      (node (ref "UNW") (pin "5") (pinfunction "VINB+_5") (pintype "input"))
    )
    (net (code "90") (name "N_SCK") (class "Default")
      (node (ref "U4") (pin "4") (pinfunction "A4_4") (pintype "bidirectional"))
      (node (ref "X-NORTH") (pin "144") (pinfunction "144_144") (pintype "bidirectional"))
    )
    (net (code "91") (name "N_SCL") (class "Default")
      (node (ref "UEP") (pin "6") (pinfunction "SCL_6") (pintype "input"))
      (node (ref "X-NORTH") (pin "143") (pinfunction "143_143") (pintype "bidirectional"))
    )
    (net (code "92") (name "N_SDA") (class "Default")
      (node (ref "UEP") (pin "5") (pinfunction "SDA_5") (pintype "bidirectional"))
      (node (ref "X-NORTH") (pin "141") (pinfunction "141_141") (pintype "bidirectional"))
    )
    (net (code "93") (name "N_SDI") (class "Default")
      (node (ref "U4") (pin "2") (pinfunction "A2_2") (pintype "bidirectional"))
      (node (ref "X-NORTH") (pin "140") (pinfunction "140_140") (pintype "bidirectional"))
    )
    (net (code "94") (name "N_SDO") (class "Default")
      (node (ref "U4") (pin "3") (pinfunction "A3_3") (pintype "bidirectional"))
      (node (ref "X-NORTH") (pin "142") (pinfunction "142_142") (pintype "bidirectional"))
    )
    (net (code "95") (name "N_SPI_EN") (class "Default")
      (node (ref "U4") (pin "1") (pinfunction "A1_1") (pintype "bidirectional"))
      (node (ref "X-NORTH") (pin "136") (pinfunction "136_136") (pintype "bidirectional"))
    )
    (net (code "96") (name "N_SPI_V") (class "Default")
      (node (ref "C59") (pin "1") (pinfunction "1_1") (pintype "passive"))
      (node (ref "U4") (pin "14") (pinfunction "VCCA_14") (pintype "power_in"))
      (node (ref "U4") (pin "15") (pinfunction "DIR1_15") (pintype "input"))
      (node (ref "U4") (pin "5") (pinfunction "DIR3_5") (pintype "input"))
      (node (ref "U4") (pin "6") (pinfunction "DIR4_6") (pintype "input"))
      (node (ref "X-NORTH") (pin "134") (pinfunction "134_134") (pintype "bidirectional"))
    )
    (net (code "97") (name "N_VE") (class "Default")
      (node (ref "C22") (pin "1") (pinfunction "1_1") (pintype "passive"))
      (node (ref "C23") (pin "1") (pinfunction "1_1") (pintype "passive"))
      (node (ref "C24") (pin "1") (pinfunction "1_1") (pintype "passive"))
      (node (ref "C25") (pin "1") (pinfunction "1_1") (pintype "passive"))
      (node (ref "C26") (pin "1") (pinfunction "1_1") (pintype "passive"))
      (node (ref "C27") (pin "1") (pinfunction "1_1") (pintype "passive"))
      (node (ref "C28") (pin "1") (pinfunction "1_1") (pintype "passive"))
      (node (ref "C50") (pin "1") (pinfunction "1_1") (pintype "passive"))
      (node (ref "C51") (pin "1") (pinfunction "1_1") (pintype "passive"))
      (node (ref "C52") (pin "1") (pinfunction "1_1") (pintype "passive"))
      (node (ref "C53") (pin "1") (pinfunction "1_1") (pintype "passive"))
      (node (ref "C54") (pin "1") (pinfunction "1_1") (pintype "passive"))
      (node (ref "C55") (pin "1") (pinfunction "1_1") (pintype "passive"))
      (node (ref "C56") (pin "1") (pinfunction "1_1") (pintype "passive"))
      (node (ref "C67") (pin "1") (pinfunction "1_1") (pintype "passive"))
      (node (ref "C69") (pin "1") (pinfunction "1_1") (pintype "passive"))
      (node (ref "C75") (pin "1") (pinfunction "1_1") (pintype "passive"))
      (node (ref "C76") (pin "1") (pinfunction "1_1") (pintype "passive"))
      (node (ref "C77") (pin "1") (pinfunction "1_1") (pintype "passive"))
      (node (ref "C84") (pin "1") (pinfunction "1_1") (pintype "passive"))
      (node (ref "C85") (pin "1") (pinfunction "1_1") (pintype "passive"))
      (node (ref "C86") (pin "1") (pinfunction "1_1") (pintype "passive"))
      (node (ref "C93") (pin "1") (pinfunction "1_1") (pintype "passive"))
      (node (ref "SENSOR") (pin "C26") (pinfunction "VDD33_C26") (pintype "power_in"))
      (node (ref "SENSOR") (pin "C27") (pinfunction "VDD33_C27") (pintype "power_in"))
      (node (ref "SENSOR") (pin "D26") (pinfunction "VDD33_D26") (pintype "power_in"))
      (node (ref "SENSOR") (pin "D3") (pinfunction "VDD33_D3") (pintype "power_in"))
      (node (ref "SENSOR") (pin "E26") (pinfunction "VDD33_E26") (pintype "power_in"))
      (node (ref "SENSOR") (pin "F26") (pinfunction "VDD33_F26") (pintype "power_in"))
      (node (ref "SENSOR") (pin "F5") (pinfunction "VDD33_F5") (pintype "power_in"))
      (node (ref "TP7") (pin "TP") (pinfunction "TP_TP") (pintype "input"))
      (node (ref "U4") (pin "13") (pinfunction "VCCB_13") (pintype "power_in"))
      (node (ref "U5") (pin "13") (pinfunction "VCCB_13") (pintype "power_in"))
      (node (ref "U6") (pin "13") (pinfunction "VCCB_13") (pintype "power_in"))
      (node (ref "X-NORTH") (pin "109") (pinfunction "109_109") (pintype "bidirectional"))
      (node (ref "X-NORTH") (pin "115") (pinfunction "115_115") (pintype "bidirectional"))
      (node (ref "X-NORTH") (pin "121") (pinfunction "121_121") (pintype "bidirectional"))
      (node (ref "X-NORTH") (pin "127") (pinfunction "127_127") (pintype "bidirectional"))
      (node (ref "X-NORTH") (pin "133") (pinfunction "133_133") (pintype "bidirectional"))
    )
    (net (code "98") (name "N_VE_CV") (class "Default")
      (node (ref "C10") (pin "1") (pinfunction "1_1") (pintype "passive"))
      (node (ref "R7") (pin "1") (pinfunction "1_1") (pintype "passive"))
      (node (ref "X-NORTH") (pin "6") (pinfunction "6_6") (pintype "bidirectional"))
    )
    (net (code "99") (name "N_VE_OV") (class "Default")
      (node (ref "UNE") (pin "7") (pinfunction "OUTB_7") (pintype "output"))
      (node (ref "X-NORTH") (pin "5") (pinfunction "5_5") (pintype "bidirectional"))
    )
    (net (code "100") (name "N_VE_UV") (class "Default")
      (node (ref "UNE") (pin "1") (pinfunction "OUTA_1") (pintype "output"))
      (node (ref "X-NORTH") (pin "11") (pinfunction "11_11") (pintype "bidirectional"))
    )
    (net (code "101") (name "N_VN") (class "Default")
      (node (ref "C31") (pin "1") (pinfunction "1_1") (pintype "passive"))
      (node (ref "C32") (pin "1") (pinfunction "1_1") (pintype "passive"))
      (node (ref "C33") (pin "1") (pinfunction "1_1") (pintype "passive"))
      (node (ref "C34") (pin "1") (pinfunction "1_1") (pintype "passive"))
      (node (ref "C35") (pin "1") (pinfunction "1_1") (pintype "passive"))
      (node (ref "C36") (pin "1") (pinfunction "1_1") (pintype "passive"))
      (node (ref "C37") (pin "1") (pinfunction "1_1") (pintype "passive"))
      (node (ref "C38") (pin "1") (pinfunction "1_1") (pintype "passive"))
      (node (ref "C39") (pin "1") (pinfunction "1_1") (pintype "passive"))
      (node (ref "C40") (pin "1") (pinfunction "1_1") (pintype "passive"))
      (node (ref "C41") (pin "1") (pinfunction "1_1") (pintype "passive"))
      (node (ref "C42") (pin "1") (pinfunction "1_1") (pintype "passive"))
      (node (ref "C43") (pin "1") (pinfunction "1_1") (pintype "passive"))
      (node (ref "C44") (pin "1") (pinfunction "1_1") (pintype "passive"))
      (node (ref "C68") (pin "1") (pinfunction "1_1") (pintype "passive"))
      (node (ref "C70") (pin "1") (pinfunction "1_1") (pintype "passive"))
      (node (ref "C78") (pin "1") (pinfunction "1_1") (pintype "passive"))
      (node (ref "C79") (pin "1") (pinfunction "1_1") (pintype "passive"))
      (node (ref "C80") (pin "1") (pinfunction "1_1") (pintype "passive"))
      (node (ref "C87") (pin "1") (pinfunction "1_1") (pintype "passive"))
      (node (ref "C88") (pin "1") (pinfunction "1_1") (pintype "passive"))
      (node (ref "C89") (pin "1") (pinfunction "1_1") (pintype "passive"))
      (node (ref "SENSOR") (pin "A10") (pinfunction "VDD18_A10") (pintype "power_in"))
      (node (ref "SENSOR") (pin "A15") (pinfunction "VDD18_A15") (pintype "power_in"))
      (node (ref "SENSOR") (pin "A16") (pinfunction "VDD18_A16") (pintype "power_in"))
      (node (ref "SENSOR") (pin "A22") (pinfunction "VDD18_A22") (pintype "power_in"))
      (node (ref "SENSOR") (pin "A26") (pinfunction "VDD18_A26") (pintype "power_in"))
      (node (ref "SENSOR") (pin "A27") (pinfunction "VDD18_A27") (pintype "power_in"))
      (node (ref "SENSOR") (pin "B4") (pinfunction "VDD18_B4") (pintype "power_in"))
      (node (ref "SENSOR") (pin "E1") (pinfunction "VDD18_PLL_E1") (pintype "power_in"))
      (node (ref "SENSOR") (pin "H10") (pinfunction "VDD18_H10") (pintype "power_in"))
      (node (ref "SENSOR") (pin "H15") (pinfunction "VDD18_H15") (pintype "power_in"))
      (node (ref "SENSOR") (pin "H16") (pinfunction "VDD18_H16") (pintype "power_in"))
      (node (ref "SENSOR") (pin "H22") (pinfunction "VDD18_H22") (pintype "power_in"))
      (node (ref "SENSOR") (pin "H26") (pinfunction "VDD18_H26") (pintype "power_in"))
      (node (ref "SENSOR") (pin "H5") (pinfunction "VDD18_H5") (pintype "power_in"))
      (node (ref "TP5") (pin "TP") (pinfunction "TP_TP") (pintype "input"))
      (node (ref "U5") (pin "14") (pinfunction "VCCA_14") (pintype "power_in"))
      (node (ref "U5") (pin "15") (pinfunction "DIR1_15") (pintype "input"))
      (node (ref "U5") (pin "16") (pinfunction "DIR2_16") (pintype "input"))
      (node (ref "U5") (pin "5") (pinfunction "DIR3_5") (pintype "input"))
      (node (ref "U6") (pin "14") (pinfunction "VCCA_14") (pintype "power_in"))
      (node (ref "U6") (pin "15") (pinfunction "DIR1_15") (pintype "input"))
      (node (ref "U6") (pin "5") (pinfunction "DIR3_5") (pintype "input"))
      (node (ref "U6") (pin "6") (pinfunction "DIR4_6") (pintype "input"))
      (node (ref "X-NORTH") (pin "49") (pinfunction "49_49") (pintype "bidirectional"))
      (node (ref "X-NORTH") (pin "55") (pinfunction "55_55") (pintype "bidirectional"))
      (node (ref "X-NORTH") (pin "61") (pinfunction "61_61") (pintype "bidirectional"))
      (node (ref "X-NORTH") (pin "67") (pinfunction "67_67") (pintype "bidirectional"))
      (node (ref "X-NORTH") (pin "73") (pinfunction "73_73") (pintype "bidirectional"))
      (node (ref "X-NORTH") (pin "79") (pinfunction "79_79") (pintype "bidirectional"))
      (node (ref "X-NORTH") (pin "85") (pinfunction "85_85") (pintype "bidirectional"))
      (node (ref "X-NORTH") (pin "91") (pinfunction "91_91") (pintype "bidirectional"))
      (node (ref "X-NORTH") (pin "97") (pinfunction "97_97") (pintype "bidirectional"))
    )
    (net (code "102") (name "N_VN_CV") (class "Default")
      (node (ref "C9") (pin "1") (pinfunction "1_1") (pintype "passive"))
      (node (ref "R4") (pin "1") (pinfunction "1_1") (pintype "passive"))
      (node (ref "X-NORTH") (pin "4") (pinfunction "4_4") (pintype "bidirectional"))
    )
    (net (code "103") (name "N_VN_OV") (class "Default")
      (node (ref "UNN") (pin "7") (pinfunction "OUTB_7") (pintype "output"))
      (node (ref "X-NORTH") (pin "3") (pinfunction "3_3") (pintype "bidirectional"))
    )
    (net (code "104") (name "N_VN_UV") (class "Default")
      (node (ref "UNN") (pin "1") (pinfunction "OUTA_1") (pintype "output"))
      (node (ref "X-NORTH") (pin "9") (pinfunction "9_9") (pintype "bidirectional"))
    )
    (net (code "105") (name "N_VW") (class "Default")
      (node (ref "C57") (pin "1") (pinfunction "1_1") (pintype "passive"))
      (node (ref "C58") (pin "1") (pinfunction "1_1") (pintype "passive"))
      (node (ref "C92") (pin "1") (pinfunction "1_1") (pintype "passive"))
      (node (ref "SENSOR") (pin "E2") (pinfunction "VDD_RES_E2") (pintype "power_in"))
      (node (ref "SENSOR") (pin "G4") (pinfunction "VDD_RES_G4") (pintype "power_in"))
      (node (ref "TP8") (pin "TP") (pinfunction "TP_TP") (pintype "input"))
      (node (ref "X-NORTH") (pin "13") (pinfunction "13_13") (pintype "bidirectional"))
      (node (ref "X-NORTH") (pin "19") (pinfunction "19_19") (pintype "bidirectional"))
      (node (ref "X-NORTH") (pin "25") (pinfunction "25_25") (pintype "bidirectional"))
      (node (ref "X-NORTH") (pin "31") (pinfunction "31_31") (pintype "bidirectional"))
      (node (ref "X-NORTH") (pin "37") (pinfunction "37_37") (pintype "bidirectional"))
    )
    (net (code "106") (name "N_VW_CV") (class "Default")
      (node (ref "C8") (pin "1") (pinfunction "1_1") (pintype "passive"))
      (node (ref "R1") (pin "1") (pinfunction "1_1") (pintype "passive"))
      (node (ref "X-NORTH") (pin "2") (pinfunction "2_2") (pintype "bidirectional"))
    )
    (net (code "107") (name "N_VW_OV") (class "Default")
      (node (ref "UNW") (pin "7") (pinfunction "OUTB_7") (pintype "output"))
      (node (ref "X-NORTH") (pin "1") (pinfunction "1_1") (pintype "bidirectional"))
    )
    (net (code "108") (name "N_VW_UV") (class "Default")
      (node (ref "UNW") (pin "1") (pinfunction "OUTA_1") (pintype "output"))
      (node (ref "X-NORTH") (pin "7") (pinfunction "7_7") (pintype "bidirectional"))
    )
    (net (code "109") (name "Net-(SENSORB-CMDN)") (class "Default")
      (node (ref "C61") (pin "1") (pinfunction "1_1") (pintype "passive"))
      (node (ref "SENSOR") (pin "F1") (pinfunction "CMDN_F1") (pintype "bidirectional"))
    )
    (net (code "110") (name "Net-(SENSORB-CMDP)") (class "Default")
      (node (ref "C22") (pin "2") (pinfunction "2_2") (pintype "passive"))
      (node (ref "SENSOR") (pin "F2") (pinfunction "CMDP_F2") (pintype "bidirectional"))
    )
    (net (code "111") (name "Net-(SENSORB-CMDP_COMP)") (class "Default")
      (node (ref "C28") (pin "2") (pinfunction "2_2") (pintype "passive"))
      (node (ref "SENSOR") (pin "H3") (pinfunction "CMDP_COMP_H3") (pintype "bidirectional"))
    )
    (net (code "112") (name "Net-(SENSORB-CMDP_COMP_INV)") (class "Default")
      (node (ref "C27") (pin "2") (pinfunction "2_2") (pintype "passive"))
      (node (ref "SENSOR") (pin "F3") (pinfunction "CMDP_COMP_INV_F3") (pintype "bidirectional"))
    )
    (net (code "113") (name "Net-(SENSORB-CMD_COLAMP)") (class "Default")
      (node (ref "C25") (pin "2") (pinfunction "2_2") (pintype "passive"))
      (node (ref "SENSOR") (pin "C6") (pinfunction "CMD_COLAMP_C6") (pintype "bidirectional"))
    )
    (net (code "114") (name "Net-(SENSORB-CMD_COL_LOAD)") (class "Default")
      (node (ref "C23") (pin "2") (pinfunction "2_2") (pintype "passive"))
      (node (ref "SENSOR") (pin "B1") (pinfunction "CMD_COL_LOAD_B1") (pintype "bidirectional"))
    )
    (net (code "115") (name "Net-(SENSORB-CMD_COL_PC)") (class "Default")
      (node (ref "C26") (pin "2") (pinfunction "2_2") (pintype "passive"))
      (node (ref "SENSOR") (pin "D1") (pinfunction "CMD_COL_PC_D1") (pintype "bidirectional"))
    )
    (net (code "116") (name "Net-(SENSORB-CMD_LVDS)") (class "Default")
      (node (ref "C62") (pin "1") (pinfunction "1_1") (pintype "passive"))
      (node (ref "SENSOR") (pin "C1") (pinfunction "CMD_LVDS_C1") (pintype "bidirectional"))
    )
    (net (code "117") (name "Net-(SENSORB-CMD_RAMP)") (class "Default")
      (node (ref "C24") (pin "2") (pinfunction "2_2") (pintype "passive"))
      (node (ref "SENSOR") (pin "B29") (pinfunction "CMD_RAMP_B29") (pintype "bidirectional"))
    )
    (net (code "118") (name "Net-(SENSORB-VBGAP)") (class "Default")
      (node (ref "C64") (pin "1") (pinfunction "1_1") (pintype "passive"))
      (node (ref "SENSOR") (pin "C29") (pinfunction "VBGAP_C29") (pintype "bidirectional"))
    )
    (net (code "119") (name "Net-(SENSORB-VCLAMP)") (class "Default")
      (node (ref "C63") (pin "1") (pinfunction "1_1") (pintype "passive"))
      (node (ref "SENSOR") (pin "D4") (pinfunction "VCLAMP_D4") (pintype "bidirectional"))
    )
    (net (code "120") (name "Net-(SENSORB-VCLAMP_ADC)") (class "Default")
      (node (ref "C60") (pin "1") (pinfunction "1_1") (pintype "passive"))
      (node (ref "SENSOR") (pin "G2") (pinfunction "VCLAMP_ADC_G2") (pintype "bidirectional"))
    )
    (net (code "121") (name "Net-(SENSORB-VPCH_H)") (class "Default")
      (node (ref "C71") (pin "1") (pinfunction "1_1") (pintype "passive"))
      (node (ref "SENSOR") (pin "C4") (pinfunction "VPCH_H_C4") (pintype "bidirectional"))
    )
    (net (code "122") (name "Net-(SENSORB-VPCH_L)") (class "Default")
      (node (ref "C14") (pin "1") (pinfunction "1_1") (pintype "passive"))
      (node (ref "SENSOR") (pin "A4") (pinfunction "VPCH_L_A4") (pintype "bidirectional"))
    )
    (net (code "123") (name "Net-(SENSORB-VREF)") (class "Default")
      (node (ref "C29") (pin "1") (pinfunction "1_1") (pintype "passive"))
      (node (ref "SENSOR") (pin "A3") (pinfunction "VREF_A3") (pintype "bidirectional"))
    )
    (net (code "124") (name "Net-(SENSORB-VREF_ADC)") (class "Default")
      (node (ref "C30") (pin "1") (pinfunction "1_1") (pintype "passive"))
      (node (ref "SENSOR") (pin "B3") (pinfunction "VREF_ADC_B3") (pintype "bidirectional"))
    )
    (net (code "125") (name "Net-(SENSORB-VRES_L)") (class "Default")
      (node (ref "C15") (pin "1") (pinfunction "1_1") (pintype "passive"))
      (node (ref "SENSOR") (pin "D5") (pinfunction "VRES_L_D5") (pintype "bidirectional"))
    )
    (net (code "126") (name "Net-(SENSORB-VTF_LOW0)") (class "Default")
      (node (ref "C18") (pin "1") (pinfunction "1_1") (pintype "passive"))
      (node (ref "SENSOR") (pin "C5") (pinfunction "VTF_LOW0_C5") (pintype "bidirectional"))
    )
    (net (code "127") (name "Net-(SENSORB-VTF_LOW1)") (class "Default")
      (node (ref "C19") (pin "1") (pinfunction "1_1") (pintype "passive"))
      (node (ref "SENSOR") (pin "D6") (pinfunction "VTF_LOW1_D6") (pintype "bidirectional"))
    )
    (net (code "128") (name "Net-(SENSORB-VTF_LOW2)") (class "Default")
      (node (ref "C20") (pin "1") (pinfunction "1_1") (pintype "passive"))
      (node (ref "SENSOR") (pin "B30") (pinfunction "VTF_LOW2_B30") (pintype "bidirectional"))
    )
    (net (code "129") (name "Net-(SENSORB-VTF_LOW3)") (class "Default")
      (node (ref "C21") (pin "1") (pinfunction "1_1") (pintype "passive"))
      (node (ref "SENSOR") (pin "C30") (pinfunction "VTF_LOW3_C30") (pintype "bidirectional"))
    )
    (net (code "130") (name "Net-(U3-ADJ)") (class "Default")
      (node (ref "R21") (pin "1") (pinfunction "1_1") (pintype "passive"))
      (node (ref "R22") (pin "2") (pinfunction "2_2") (pintype "passive"))
      (node (ref "U3") (pin "5") (pinfunction "ADJ_5") (pintype "input"))
    )
    (net (code "131") (name "Net-(U6-B4)") (class "Default")
      (node (ref "TP9") (pin "TP") (pinfunction "TP_TP") (pintype "input"))
      (node (ref "U6") (pin "9") (pinfunction "B4_9") (pintype "bidirectional"))
    )
    (net (code "132") (name "Net-(UEP-WP)") (class "Default")
      (node (ref "R1X") (pin "2") (pinfunction "2_2") (pintype "passive"))
      (node (ref "R2X") (pin "1") (pinfunction "1_1") (pintype "passive"))
      (node (ref "UEP") (pin "7") (pinfunction "WP_7") (pintype "input"))
    )
    (net (code "133") (name "Net-(UNE-VINA+)") (class "Default")
      (node (ref "R7") (pin "2") (pinfunction "2_2") (pintype "passive"))
      (node (ref "R8") (pin "1") (pinfunction "1_1") (pintype "passive"))
      (node (ref "UNE") (pin "3") (pinfunction "VINA+_3") (pintype "input"))
    )
    (net (code "134") (name "Net-(UNE-VINB-)") (class "Default")
      (node (ref "R8") (pin "2") (pinfunction "2_2") (pintype "passive"))
      (node (ref "R9") (pin "1") (pinfunction "1_1") (pintype "passive"))
      (node (ref "UNE") (pin "6") (pinfunction "VINB-_6") (pintype "input"))
    )
    (net (code "135") (name "Net-(UNN-VINA+)") (class "Default")
      (node (ref "R4") (pin "2") (pinfunction "2_2") (pintype "passive"))
      (node (ref "R5") (pin "1") (pinfunction "1_1") (pintype "passive"))
      (node (ref "UNN") (pin "3") (pinfunction "VINA+_3") (pintype "input"))
    )
    (net (code "136") (name "Net-(UNN-VINB-)") (class "Default")
      (node (ref "R5") (pin "2") (pinfunction "2_2") (pintype "passive"))
      (node (ref "R6") (pin "1") (pinfunction "1_1") (pintype "passive"))
      (node (ref "UNN") (pin "6") (pinfunction "VINB-_6") (pintype "input"))
    )
    (net (code "137") (name "Net-(UNW-VINA+)") (class "Default")
      (node (ref "R1") (pin "2") (pinfunction "2_2") (pintype "passive"))
      (node (ref "R2") (pin "1") (pinfunction "1_1") (pintype "passive"))
      (node (ref "UNW") (pin "3") (pinfunction "VINA+_3") (pintype "input"))
    )
    (net (code "138") (name "Net-(UNW-VINB-)") (class "Default")
      (node (ref "R2") (pin "2") (pinfunction "2_2") (pintype "passive"))
      (node (ref "R3") (pin "1") (pinfunction "1_1") (pintype "passive"))
      (node (ref "UNW") (pin "6") (pinfunction "VINB-_6") (pintype "input"))
    )
    (net (code "139") (name "Net-(USE-VINA+)") (class "Default")
      (node (ref "R10") (pin "2") (pinfunction "2_2") (pintype "passive"))
      (node (ref "R11") (pin "1") (pinfunction "1_1") (pintype "passive"))
      (node (ref "USE") (pin "3") (pinfunction "VINA+_3") (pintype "input"))
    )
    (net (code "140") (name "Net-(USE-VINB-)") (class "Default")
      (node (ref "R11") (pin "2") (pinfunction "2_2") (pintype "passive"))
      (node (ref "R12") (pin "1") (pinfunction "1_1") (pintype "passive"))
      (node (ref "USE") (pin "6") (pinfunction "VINB-_6") (pintype "input"))
    )
    (net (code "141") (name "Net-(USS-VINA+)") (class "Default")
      (node (ref "R13") (pin "2") (pinfunction "2_2") (pintype "passive"))
      (node (ref "R14") (pin "1") (pinfunction "1_1") (pintype "passive"))
      (node (ref "USS") (pin "3") (pinfunction "VINA+_3") (pintype "input"))
    )
    (net (code "142") (name "Net-(USS-VINB-)") (class "Default")
      (node (ref "R14") (pin "2") (pinfunction "2_2") (pintype "passive"))
      (node (ref "R15") (pin "1") (pinfunction "1_1") (pintype "passive"))
      (node (ref "USS") (pin "6") (pinfunction "VINB-_6") (pintype "input"))
    )
    (net (code "143") (name "Net-(USW-VINA+)") (class "Default")
      (node (ref "R16") (pin "2") (pinfunction "2_2") (pintype "passive"))
      (node (ref "R17") (pin "1") (pinfunction "1_1") (pintype "passive"))
      (node (ref "USW") (pin "3") (pinfunction "VINA+_3") (pintype "input"))
    )
    (net (code "144") (name "Net-(USW-VINB-)") (class "Default")
      (node (ref "R17") (pin "2") (pinfunction "2_2") (pintype "passive"))
      (node (ref "R18") (pin "1") (pinfunction "1_1") (pintype "passive"))
      (node (ref "USW") (pin "6") (pinfunction "VINB-_6") (pintype "input"))
    )
    (net (code "145") (name "S00_N") (class "Default")
      (node (ref "X-SOUTH") (pin "16") (pinfunction "16_16") (pintype "bidirectional"))
    )
    (net (code "146") (name "S00_P") (class "Default")
      (node (ref "X-SOUTH") (pin "14") (pinfunction "14_14") (pintype "bidirectional"))
    )
    (net (code "147") (name "S01_N") (class "Default")
      (node (ref "X-SOUTH") (pin "17") (pinfunction "17_17") (pintype "bidirectional"))
    )
    (net (code "148") (name "S01_P") (class "Default")
      (node (ref "X-SOUTH") (pin "15") (pinfunction "15_15") (pintype "bidirectional"))
    )
    (net (code "149") (name "S02_N") (class "Default")
      (node (ref "X-SOUTH") (pin "22") (pinfunction "22_22") (pintype "bidirectional"))
    )
    (net (code "150") (name "S02_P") (class "Default")
      (node (ref "X-SOUTH") (pin "20") (pinfunction "20_20") (pintype "bidirectional"))
    )
    (net (code "151") (name "S03_N") (class "Default")
      (node (ref "X-SOUTH") (pin "23") (pinfunction "23_23") (pintype "bidirectional"))
    )
    (net (code "152") (name "S03_P") (class "Default")
      (node (ref "X-SOUTH") (pin "21") (pinfunction "21_21") (pintype "bidirectional"))
    )
    (net (code "153") (name "S04_N") (class "Default")
      (node (ref "SENSOR") (pin "C24") (pinfunction "OUT32_N_C24") (pintype "output"))
      (node (ref "X-SOUTH") (pin "28") (pinfunction "28_28") (pintype "bidirectional"))
    )
    (net (code "154") (name "S04_P") (class "Default")
      (node (ref "SENSOR") (pin "C25") (pinfunction "OUT32_P_C25") (pintype "output"))
      (node (ref "X-SOUTH") (pin "26") (pinfunction "26_26") (pintype "bidirectional"))
    )
    (net (code "155") (name "S05_N") (class "Default")
      (node (ref "X-SOUTH") (pin "29") (pinfunction "29_29") (pintype "bidirectional"))
    )
    (net (code "156") (name "S05_P") (class "Default")
      (node (ref "X-SOUTH") (pin "27") (pinfunction "27_27") (pintype "bidirectional"))
    )
    (net (code "157") (name "S06_N") (class "Default")
      (node (ref "SENSOR") (pin "D23") (pinfunction "OUT30_N_D23") (pintype "output"))
      (node (ref "X-SOUTH") (pin "34") (pinfunction "34_34") (pintype "bidirectional"))
    )
    (net (code "158") (name "S06_P") (class "Default")
      (node (ref "SENSOR") (pin "D24") (pinfunction "OUT30_P_D24") (pintype "output"))
      (node (ref "X-SOUTH") (pin "32") (pinfunction "32_32") (pintype "bidirectional"))
    )
    (net (code "159") (name "S07_N") (class "Default")
      (node (ref "SENSOR") (pin "B24") (pinfunction "OUT31_N_B24") (pintype "output"))
      (node (ref "X-SOUTH") (pin "35") (pinfunction "35_35") (pintype "bidirectional"))
    )
    (net (code "160") (name "S07_P") (class "Default")
      (node (ref "SENSOR") (pin "B25") (pinfunction "OUT31_P_B25") (pintype "output"))
      (node (ref "X-SOUTH") (pin "33") (pinfunction "33_33") (pintype "bidirectional"))
    )
    (net (code "161") (name "S08_N") (class "Default")
      (node (ref "SENSOR") (pin "D21") (pinfunction "OUT27_N_D21") (pintype "output"))
      (node (ref "X-SOUTH") (pin "40") (pinfunction "40_40") (pintype "bidirectional"))
    )
    (net (code "162") (name "S08_P") (class "Default")
      (node (ref "SENSOR") (pin "D22") (pinfunction "OUT27_P_D22") (pintype "output"))
      (node (ref "X-SOUTH") (pin "38") (pinfunction "38_38") (pintype "bidirectional"))
    )
    (net (code "163") (name "S09_N") (class "Default")
      (node (ref "SENSOR") (pin "A23") (pinfunction "OUT29_N_A23") (pintype "output"))
      (node (ref "X-SOUTH") (pin "41") (pinfunction "41_41") (pintype "bidirectional"))
    )
    (net (code "164") (name "S09_P") (class "Default")
      (node (ref "SENSOR") (pin "A24") (pinfunction "OUT29_P_A24") (pintype "output"))
      (node (ref "X-SOUTH") (pin "39") (pinfunction "39_39") (pintype "bidirectional"))
    )
    (net (code "165") (name "S10_N") (class "Default")
      (node (ref "SENSOR") (pin "C21") (pinfunction "OUT28_N_C21") (pintype "output"))
      (node (ref "X-SOUTH") (pin "46") (pinfunction "46_46") (pintype "bidirectional"))
    )
    (net (code "166") (name "S10_P") (class "Default")
      (node (ref "SENSOR") (pin "C22") (pinfunction "OUT28_P_C22") (pintype "output"))
      (node (ref "X-SOUTH") (pin "44") (pinfunction "44_44") (pintype "bidirectional"))
    )
    (net (code "167") (name "S11_N") (class "Default")
      (node (ref "SENSOR") (pin "B20") (pinfunction "OUT26_N_B20") (pintype "output"))
      (node (ref "X-SOUTH") (pin "47") (pinfunction "47_47") (pintype "bidirectional"))
    )
    (net (code "168") (name "S11_P") (class "Default")
      (node (ref "SENSOR") (pin "B21") (pinfunction "OUT26_P_B21") (pintype "output"))
      (node (ref "X-SOUTH") (pin "45") (pinfunction "45_45") (pintype "bidirectional"))
    )
    (net (code "169") (name "S12_N") (class "Default")
      (node (ref "SENSOR") (pin "D19") (pinfunction "OUT24_N_D19") (pintype "output"))
      (node (ref "X-SOUTH") (pin "52") (pinfunction "52_52") (pintype "bidirectional"))
    )
    (net (code "170") (name "S12_P") (class "Default")
      (node (ref "SENSOR") (pin "D20") (pinfunction "OUT24_P_D20") (pintype "output"))
      (node (ref "X-SOUTH") (pin "50") (pinfunction "50_50") (pintype "bidirectional"))
    )
    (net (code "171") (name "S13_N") (class "Default")
      (node (ref "SENSOR") (pin "A19") (pinfunction "OUT23_N_A19") (pintype "output"))
      (node (ref "X-SOUTH") (pin "53") (pinfunction "53_53") (pintype "bidirectional"))
    )
    (net (code "172") (name "S13_P") (class "Default")
      (node (ref "SENSOR") (pin "A20") (pinfunction "OUT23_P_A20") (pintype "output"))
      (node (ref "X-SOUTH") (pin "51") (pinfunction "51_51") (pintype "bidirectional"))
    )
    (net (code "173") (name "S14_N") (class "Default")
      (node (ref "SENSOR") (pin "C19") (pinfunction "OUT25_N_C19") (pintype "output"))
      (node (ref "X-SOUTH") (pin "58") (pinfunction "58_58") (pintype "bidirectional"))
    )
    (net (code "174") (name "S14_P") (class "Default")
      (node (ref "SENSOR") (pin "C20") (pinfunction "OUT25_P_C20") (pintype "output"))
      (node (ref "X-SOUTH") (pin "56") (pinfunction "56_56") (pintype "bidirectional"))
    )
    (net (code "175") (name "S15_N") (class "Default")
      (node (ref "SENSOR") (pin "B18") (pinfunction "OUT22_N_B18") (pintype "output"))
      (node (ref "X-SOUTH") (pin "59") (pinfunction "59_59") (pintype "bidirectional"))
    )
    (net (code "176") (name "S15_P") (class "Default")
      (node (ref "SENSOR") (pin "B19") (pinfunction "OUT22_P_B19") (pintype "output"))
      (node (ref "X-SOUTH") (pin "57") (pinfunction "57_57") (pintype "bidirectional"))
    )
    (net (code "177") (name "S16_N") (class "Default")
      (node (ref "SENSOR") (pin "C17") (pinfunction "OUT21_N_C17") (pintype "output"))
      (node (ref "X-SOUTH") (pin "64") (pinfunction "64_64") (pintype "bidirectional"))
    )
    (net (code "178") (name "S16_P") (class "Default")
      (node (ref "SENSOR") (pin "C18") (pinfunction "OUT21_P_C18") (pintype "output"))
      (node (ref "X-SOUTH") (pin "62") (pinfunction "62_62") (pintype "bidirectional"))
    )
    (net (code "179") (name "S17_N") (class "Default")
      (node (ref "SENSOR") (pin "A17") (pinfunction "OUT19_N_A17") (pintype "output"))
      (node (ref "X-SOUTH") (pin "65") (pinfunction "65_65") (pintype "bidirectional"))
    )
    (net (code "180") (name "S17_P") (class "Default")
      (node (ref "SENSOR") (pin "A18") (pinfunction "OUT19_P_A18") (pintype "output"))
      (node (ref "X-SOUTH") (pin "63") (pinfunction "63_63") (pintype "bidirectional"))
    )
    (net (code "181") (name "S18_N") (class "Default")
      (node (ref "SENSOR") (pin "D17") (pinfunction "OUT20_N_D17") (pintype "output"))
      (node (ref "X-SOUTH") (pin "70") (pinfunction "70_70") (pintype "bidirectional"))
    )
    (net (code "182") (name "S18_P") (class "Default")
      (node (ref "SENSOR") (pin "D18") (pinfunction "OUT20_P_D18") (pintype "output"))
      (node (ref "X-SOUTH") (pin "68") (pinfunction "68_68") (pintype "bidirectional"))
    )
    (net (code "183") (name "S19_N") (class "Default")
      (node (ref "SENSOR") (pin "B16") (pinfunction "OUT18_N_B16") (pintype "output"))
      (node (ref "X-SOUTH") (pin "71") (pinfunction "71_71") (pintype "bidirectional"))
    )
    (net (code "184") (name "S19_P") (class "Default")
      (node (ref "SENSOR") (pin "B17") (pinfunction "OUT18_P_B17") (pintype "output"))
      (node (ref "X-SOUTH") (pin "69") (pinfunction "69_69") (pintype "bidirectional"))
    )
    (net (code "185") (name "S20_N") (class "Default")
      (node (ref "SENSOR") (pin "D15") (pinfunction "OUT17_N_D15") (pintype "output"))
      (node (ref "X-SOUTH") (pin "76") (pinfunction "76_76") (pintype "bidirectional"))
    )
    (net (code "186") (name "S20_P") (class "Default")
      (node (ref "SENSOR") (pin "D16") (pinfunction "OUT17_P_D16") (pintype "output"))
      (node (ref "X-SOUTH") (pin "74") (pinfunction "74_74") (pintype "bidirectional"))
    )
    (net (code "187") (name "S21_N") (class "Default")
      (node (ref "SENSOR") (pin "B14") (pinfunction "OUT16_N_B14") (pintype "output"))
      (node (ref "X-SOUTH") (pin "77") (pinfunction "77_77") (pintype "bidirectional"))
    )
    (net (code "188") (name "S21_P") (class "Default")
      (node (ref "SENSOR") (pin "B15") (pinfunction "OUT16_P_B15") (pintype "output"))
      (node (ref "X-SOUTH") (pin "75") (pinfunction "75_75") (pintype "bidirectional"))
    )
    (net (code "189") (name "S22_N") (class "Default")
      (node (ref "SENSOR") (pin "D13") (pinfunction "OUT15_N_D13") (pintype "output"))
      (node (ref "X-SOUTH") (pin "82") (pinfunction "82_82") (pintype "bidirectional"))
    )
    (net (code "190") (name "S22_P") (class "Default")
      (node (ref "SENSOR") (pin "D14") (pinfunction "OUT15_P_D14") (pintype "output"))
      (node (ref "X-SOUTH") (pin "80") (pinfunction "80_80") (pintype "bidirectional"))
    )
    (net (code "191") (name "S23_N") (class "Default")
      (node (ref "SENSOR") (pin "A13") (pinfunction "OUT13_N_A13") (pintype "output"))
      (node (ref "X-SOUTH") (pin "83") (pinfunction "83_83") (pintype "bidirectional"))
    )
    (net (code "192") (name "S23_P") (class "Default")
      (node (ref "SENSOR") (pin "A14") (pinfunction "OUT13_P_A14") (pintype "output"))
      (node (ref "X-SOUTH") (pin "81") (pinfunction "81_81") (pintype "bidirectional"))
    )
    (net (code "193") (name "S24_N") (class "Default")
      (node (ref "SENSOR") (pin "C13") (pinfunction "OUT14_N_C13") (pintype "output"))
      (node (ref "X-SOUTH") (pin "88") (pinfunction "88_88") (pintype "bidirectional"))
    )
    (net (code "194") (name "S24_P") (class "Default")
      (node (ref "SENSOR") (pin "C14") (pinfunction "OUT14_P_C14") (pintype "output"))
      (node (ref "X-SOUTH") (pin "86") (pinfunction "86_86") (pintype "bidirectional"))
    )
    (net (code "195") (name "S25_N") (class "Default")
      (node (ref "SENSOR") (pin "B12") (pinfunction "OUT12_N_B12") (pintype "output"))
      (node (ref "X-SOUTH") (pin "89") (pinfunction "89_89") (pintype "bidirectional"))
    )
    (net (code "196") (name "S25_P") (class "Default")
      (node (ref "SENSOR") (pin "B13") (pinfunction "OUT12_P_B13") (pintype "output"))
      (node (ref "X-SOUTH") (pin "87") (pinfunction "87_87") (pintype "bidirectional"))
    )
    (net (code "197") (name "S26_N") (class "Default")
      (node (ref "SENSOR") (pin "D11") (pinfunction "OUT10_N_D11") (pintype "output"))
      (node (ref "X-SOUTH") (pin "94") (pinfunction "94_94") (pintype "bidirectional"))
    )
    (net (code "198") (name "S26_P") (class "Default")
      (node (ref "SENSOR") (pin "D12") (pinfunction "OUT10_P_D12") (pintype "output"))
      (node (ref "X-SOUTH") (pin "92") (pinfunction "92_92") (pintype "bidirectional"))
    )
    (net (code "199") (name "S27_N") (class "Default")
      (node (ref "SENSOR") (pin "A11") (pinfunction "OUT9_N_A11") (pintype "output"))
      (node (ref "X-SOUTH") (pin "95") (pinfunction "95_95") (pintype "bidirectional"))
    )
    (net (code "200") (name "S27_P") (class "Default")
      (node (ref "SENSOR") (pin "A12") (pinfunction "OUT9_P_A12") (pintype "output"))
      (node (ref "X-SOUTH") (pin "93") (pinfunction "93_93") (pintype "bidirectional"))
    )
    (net (code "201") (name "S28_N") (class "Default")
      (node (ref "SENSOR") (pin "C11") (pinfunction "OUT11_N_C11") (pintype "output"))
      (node (ref "X-SOUTH") (pin "100") (pinfunction "100_100") (pintype "bidirectional"))
    )
    (net (code "202") (name "S28_P") (class "Default")
      (node (ref "SENSOR") (pin "C12") (pinfunction "OUT11_P_C12") (pintype "output"))
      (node (ref "X-SOUTH") (pin "98") (pinfunction "98_98") (pintype "bidirectional"))
    )
    (net (code "203") (name "S29_N") (class "Default")
      (node (ref "SENSOR") (pin "B10") (pinfunction "OUT8_N_B10") (pintype "output"))
      (node (ref "X-SOUTH") (pin "101") (pinfunction "101_101") (pintype "bidirectional"))
    )
    (net (code "204") (name "S29_P") (class "Default")
      (node (ref "SENSOR") (pin "B11") (pinfunction "OUT8_P_B11") (pintype "output"))
      (node (ref "X-SOUTH") (pin "99") (pinfunction "99_99") (pintype "bidirectional"))
    )
    (net (code "205") (name "S30_N") (class "Default")
      (node (ref "SENSOR") (pin "C9") (pinfunction "OUT7_N_C9") (pintype "output"))
      (node (ref "X-SOUTH") (pin "106") (pinfunction "106_106") (pintype "bidirectional"))
    )
    (net (code "206") (name "S30_P") (class "Default")
      (node (ref "SENSOR") (pin "C10") (pinfunction "OUT7_P_C10") (pintype "output"))
      (node (ref "X-SOUTH") (pin "104") (pinfunction "104_104") (pintype "bidirectional"))
    )
    (net (code "207") (name "S31_N") (class "Default")
      (node (ref "SENSOR") (pin "B8") (pinfunction "OUT5_N_B8") (pintype "output"))
      (node (ref "X-SOUTH") (pin "107") (pinfunction "107_107") (pintype "bidirectional"))
    )
    (net (code "208") (name "S31_P") (class "Default")
      (node (ref "SENSOR") (pin "B9") (pinfunction "OUT5_P_B9") (pintype "output"))
      (node (ref "X-SOUTH") (pin "105") (pinfunction "105_105") (pintype "bidirectional"))
    )
    (net (code "209") (name "S32_N") (class "Default")
      (node (ref "SENSOR") (pin "D9") (pinfunction "OUT6_N_D9") (pintype "output"))
      (node (ref "X-SOUTH") (pin "112") (pinfunction "112_112") (pintype "bidirectional"))
    )
    (net (code "210") (name "S32_P") (class "Default")
      (node (ref "SENSOR") (pin "D10") (pinfunction "OUT6_P_D10") (pintype "output"))
      (node (ref "X-SOUTH") (pin "110") (pinfunction "110_110") (pintype "bidirectional"))
    )
    (net (code "211") (name "S33_N") (class "Default")
      (node (ref "SENSOR") (pin "A7") (pinfunction "OUT2_N_A7") (pintype "output"))
      (node (ref "X-SOUTH") (pin "113") (pinfunction "113_113") (pintype "bidirectional"))
    )
    (net (code "212") (name "S33_P") (class "Default")
      (node (ref "SENSOR") (pin "A8") (pinfunction "OUT2_P_A8") (pintype "output"))
      (node (ref "X-SOUTH") (pin "111") (pinfunction "111_111") (pintype "bidirectional"))
    )
    (net (code "213") (name "S34_N") (class "Default")
      (node (ref "SENSOR") (pin "C7") (pinfunction "OUT4_N_C7") (pintype "output"))
      (node (ref "X-SOUTH") (pin "118") (pinfunction "118_118") (pintype "bidirectional"))
    )
    (net (code "214") (name "S34_P") (class "Default")
      (node (ref "SENSOR") (pin "C8") (pinfunction "OUT4_P_C8") (pintype "output"))
      (node (ref "X-SOUTH") (pin "116") (pinfunction "116_116") (pintype "bidirectional"))
    )
    (net (code "215") (name "S35_N") (class "Default")
      (node (ref "SENSOR") (pin "B6") (pinfunction "OUT1_N_B6") (pintype "output"))
      (node (ref "X-SOUTH") (pin "119") (pinfunction "119_119") (pintype "bidirectional"))
    )
    (net (code "216") (name "S35_P") (class "Default")
      (node (ref "SENSOR") (pin "B7") (pinfunction "OUT1_P_B7") (pintype "output"))
      (node (ref "X-SOUTH") (pin "117") (pinfunction "117_117") (pintype "bidirectional"))
    )
    (net (code "217") (name "S36_N") (class "Default")
      (node (ref "SENSOR") (pin "D7") (pinfunction "OUT3_N_D7") (pintype "output"))
      (node (ref "X-SOUTH") (pin "124") (pinfunction "124_124") (pintype "bidirectional"))
    )
    (net (code "218") (name "S36_P") (class "Default")
      (node (ref "SENSOR") (pin "D8") (pinfunction "OUT3_P_D8") (pintype "output"))
      (node (ref "X-SOUTH") (pin "122") (pinfunction "122_122") (pintype "bidirectional"))
    )
    (net (code "219") (name "S37_N") (class "Default")
      (node (ref "SENSOR") (pin "A5") (pinfunction "OUTCTR_N_A5") (pintype "output"))
      (node (ref "X-SOUTH") (pin "125") (pinfunction "125_125") (pintype "bidirectional"))
    )
    (net (code "220") (name "S37_P") (class "Default")
      (node (ref "SENSOR") (pin "A6") (pinfunction "OUTCTR_P_A6") (pintype "output"))
      (node (ref "X-SOUTH") (pin "123") (pinfunction "123_123") (pintype "bidirectional"))
    )
    (net (code "221") (name "S38_N") (class "Default")
      (node (ref "X-SOUTH") (pin "130") (pinfunction "130_130") (pintype "bidirectional"))
    )
    (net (code "222") (name "S38_P") (class "Default")
      (node (ref "X-SOUTH") (pin "128") (pinfunction "128_128") (pintype "bidirectional"))
    )
    (net (code "223") (name "S39_N") (class "Default")
      (node (ref "U3") (pin "6") (pinfunction "EN_6") (pintype "input"))
      (node (ref "X-SOUTH") (pin "131") (pinfunction "131_131") (pintype "bidirectional"))
    )
    (net (code "224") (name "S39_P") (class "Default")
      (node (ref "X-SOUTH") (pin "129") (pinfunction "129_129") (pintype "bidirectional"))
    )
    (net (code "225") (name "SPI_CLK") (class "Default")
      (node (ref "SENSOR") (pin "H29") (pinfunction "SPI_CLK_H29") (pintype "input"))
      (node (ref "U4") (pin "9") (pinfunction "B4_9") (pintype "bidirectional"))
    )
    (net (code "226") (name "SPI_EN") (class "Default")
      (node (ref "SENSOR") (pin "F28") (pinfunction "SPI_EN_F28") (pintype "input"))
      (node (ref "U4") (pin "12") (pinfunction "B1_12") (pintype "bidirectional"))
    )
    (net (code "227") (name "SPI_IN") (class "Default")
      (node (ref "SENSOR") (pin "E28") (pinfunction "SPI_IN_E28") (pintype "input"))
      (node (ref "U4") (pin "10") (pinfunction "B3_10") (pintype "bidirectional"))
    )
    (net (code "228") (name "SPI_OUT") (class "Default")
      (node (ref "SENSOR") (pin "G28") (pinfunction "SPI_OUT_G28") (pintype "output"))
      (node (ref "U4") (pin "11") (pinfunction "B2_11") (pintype "bidirectional"))
    )
    (net (code "229") (name "SYS_RES_N") (class "Default")
      (node (ref "SENSOR") (pin "F30") (pinfunction "SYS_RES_N_F30") (pintype "input"))
      (node (ref "U5") (pin "10") (pinfunction "B3_10") (pintype "bidirectional"))
    )
    (net (code "230") (name "S_CHK_EN") (class "Default")
      (node (ref "X-SOUTH") (pin "8") (pinfunction "8_8") (pintype "bidirectional"))
    )
    (net (code "231") (name "S_CHK_V") (class "Default")
      (node (ref "C5") (pin "1") (pinfunction "1_1") (pintype "passive"))
      (node (ref "C6") (pin "1") (pinfunction "1_1") (pintype "passive"))
      (node (ref "C7") (pin "1") (pinfunction "1_1") (pintype "passive"))
      (node (ref "R20") (pin "1") (pinfunction "1_1") (pintype "passive"))
      (node (ref "TP3") (pin "TP") (pinfunction "TP_TP") (pintype "input"))
      (node (ref "USE") (pin "8") (pinfunction "VDD_8") (pintype "power_in"))
      (node (ref "USS") (pin "8") (pinfunction "VDD_8") (pintype "power_in"))
      (node (ref "USW") (pin "8") (pinfunction "VDD_8") (pintype "power_in"))
      (node (ref "X-SOUTH") (pin "10") (pinfunction "10_10") (pintype "bidirectional"))
    )
    (net (code "232") (name "S_I2C_EN") (class "Default")
      (node (ref "X-SOUTH") (pin "137") (pinfunction "137_137") (pintype "bidirectional"))
    )
    (net (code "233") (name "S_I2C_V") (class "Default")
      (node (ref "U7") (pin "8") (pinfunction "VCC_8") (pintype "power_in"))
      (node (ref "X-SOUTH") (pin "135") (pinfunction "135_135") (pintype "bidirectional"))
    )
    (net (code "234") (name "S_REF") (class "Default")
      (node (ref "R20") (pin "2") (pinfunction "2_2") (pintype "passive"))
      (node (ref "TP4") (pin "TP") (pinfunction "TP_TP") (pintype "input"))
      (node (ref "U2") (pin "1") (pinfunction "CATHODE_1") (pintype "output"))
      (node (ref "U2") (pin "3") (pinfunction "REF_3") (pintype "input"))
      (node (ref "USE") (pin "2") (pinfunction "VINA-_2") (pintype "input"))
      (node (ref "USE") (pin "5") (pinfunction "VINB+_5") (pintype "input"))
      (node (ref "USS") (pin "2") (pinfunction "VINA-_2") (pintype "input"))
      (node (ref "USS") (pin "5") (pinfunction "VINB+_5") (pintype "input"))
      (node (ref "USW") (pin "2") (pinfunction "VINA-_2") (pintype "input"))
      (node (ref "USW") (pin "5") (pinfunction "VINB+_5") (pintype "input"))
    )
    (net (code "235") (name "S_SCK") (class "Default")
      (node (ref "X-SOUTH") (pin "144") (pinfunction "144_144") (pintype "bidirectional"))
    )
    (net (code "236") (name "S_SCL") (class "Default")
      (node (ref "U7") (pin "2") (pinfunction "SCL_2") (pintype "input"))
      (node (ref "X-SOUTH") (pin "143") (pinfunction "143_143") (pintype "bidirectional"))
    )
    (net (code "237") (name "S_SDA") (class "Default")
      (node (ref "U7") (pin "1") (pinfunction "SDA_1") (pintype "bidirectional"))
      (node (ref "X-SOUTH") (pin "141") (pinfunction "141_141") (pintype "bidirectional"))
    )
    (net (code "238") (name "S_SDI") (class "Default")
      (node (ref "X-SOUTH") (pin "140") (pinfunction "140_140") (pintype "bidirectional"))
    )
    (net (code "239") (name "S_SDO") (class "Default")
      (node (ref "X-SOUTH") (pin "142") (pinfunction "142_142") (pintype "bidirectional"))
    )
    (net (code "240") (name "S_SPI_EN") (class "Default")
      (node (ref "X-SOUTH") (pin "136") (pinfunction "136_136") (pintype "bidirectional"))
    )
    (net (code "241") (name "S_SPI_V") (class "Default")
      (node (ref "X-SOUTH") (pin "134") (pinfunction "134_134") (pintype "bidirectional"))
    )
    (net (code "242") (name "S_VE") (class "Default")
      (node (ref "X-SOUTH") (pin "13") (pinfunction "13_13") (pintype "bidirectional"))
      (node (ref "X-SOUTH") (pin "19") (pinfunction "19_19") (pintype "bidirectional"))
      (node (ref "X-SOUTH") (pin "25") (pinfunction "25_25") (pintype "bidirectional"))
      (node (ref "X-SOUTH") (pin "31") (pinfunction "31_31") (pintype "bidirectional"))
      (node (ref "X-SOUTH") (pin "37") (pinfunction "37_37") (pintype "bidirectional"))
    )
    (net (code "243") (name "S_VE_CV") (class "Default")
      (node (ref "C11") (pin "1") (pinfunction "1_1") (pintype "passive"))
      (node (ref "R10") (pin "1") (pinfunction "1_1") (pintype "passive"))
      (node (ref "X-SOUTH") (pin "2") (pinfunction "2_2") (pintype "bidirectional"))
    )
    (net (code "244") (name "S_VE_OV") (class "Default")
      (node (ref "USE") (pin "7") (pinfunction "OUTB_7") (pintype "output"))
      (node (ref "X-SOUTH") (pin "1") (pinfunction "1_1") (pintype "bidirectional"))
    )
    (net (code "245") (name "S_VE_UV") (class "Default")
      (node (ref "USE") (pin "1") (pinfunction "OUTA_1") (pintype "output"))
      (node (ref "X-SOUTH") (pin "7") (pinfunction "7_7") (pintype "bidirectional"))
    )
    (net (code "246") (name "S_VS") (class "Default")
      (node (ref "C45") (pin "1") (pinfunction "1_1") (pintype "passive"))
      (node (ref "C46") (pin "1") (pinfunction "1_1") (pintype "passive"))
      (node (ref "C47") (pin "1") (pinfunction "1_1") (pintype "passive"))
      (node (ref "C48") (pin "1") (pinfunction "1_1") (pintype "passive"))
      (node (ref "C49") (pin "1") (pinfunction "1_1") (pintype "passive"))
      (node (ref "C72") (pin "1") (pinfunction "1_1") (pintype "passive"))
      (node (ref "C73") (pin "1") (pinfunction "1_1") (pintype "passive"))
      (node (ref "C74") (pin "1") (pinfunction "1_1") (pintype "passive"))
      (node (ref "C81") (pin "1") (pinfunction "1_1") (pintype "passive"))
      (node (ref "C82") (pin "1") (pinfunction "1_1") (pintype "passive"))
      (node (ref "C83") (pin "1") (pinfunction "1_1") (pintype "passive"))
      (node (ref "SENSOR") (pin "A30") (pinfunction "VDD_PIX_A30") (pintype "power_in"))
      (node (ref "SENSOR") (pin "D28") (pinfunction "VDD_PIX_D28") (pintype "power_in"))
      (node (ref "SENSOR") (pin "D30") (pinfunction "VDD_PIX_D30") (pintype "power_in"))
      (node (ref "SENSOR") (pin "G1") (pinfunction "VDD_PIX_G1") (pintype "power_in"))
      (node (ref "SENSOR") (pin "H28") (pinfunction "VDD_PIX_H28") (pintype "power_in"))
      (node (ref "TP6") (pin "TP") (pinfunction "TP_TP") (pintype "input"))
      (node (ref "X-SOUTH") (pin "49") (pinfunction "49_49") (pintype "bidirectional"))
      (node (ref "X-SOUTH") (pin "55") (pinfunction "55_55") (pintype "bidirectional"))
      (node (ref "X-SOUTH") (pin "61") (pinfunction "61_61") (pintype "bidirectional"))
      (node (ref "X-SOUTH") (pin "67") (pinfunction "67_67") (pintype "bidirectional"))
      (node (ref "X-SOUTH") (pin "73") (pinfunction "73_73") (pintype "bidirectional"))
      (node (ref "X-SOUTH") (pin "79") (pinfunction "79_79") (pintype "bidirectional"))
      (node (ref "X-SOUTH") (pin "85") (pinfunction "85_85") (pintype "bidirectional"))
      (node (ref "X-SOUTH") (pin "91") (pinfunction "91_91") (pintype "bidirectional"))
      (node (ref "X-SOUTH") (pin "97") (pinfunction "97_97") (pintype "bidirectional"))
    )
    (net (code "247") (name "S_VS_CV") (class "Default")
      (node (ref "C12") (pin "1") (pinfunction "1_1") (pintype "passive"))
      (node (ref "R13") (pin "1") (pinfunction "1_1") (pintype "passive"))
      (node (ref "X-SOUTH") (pin "4") (pinfunction "4_4") (pintype "bidirectional"))
    )
    (net (code "248") (name "S_VS_OV") (class "Default")
      (node (ref "USS") (pin "7") (pinfunction "OUTB_7") (pintype "output"))
      (node (ref "X-SOUTH") (pin "3") (pinfunction "3_3") (pintype "bidirectional"))
    )
    (net (code "249") (name "S_VS_UV") (class "Default")
      (node (ref "USS") (pin "1") (pinfunction "OUTA_1") (pintype "output"))
      (node (ref "X-SOUTH") (pin "9") (pinfunction "9_9") (pintype "bidirectional"))
    )
    (net (code "250") (name "S_VW") (class "Default")
      (node (ref "C90") (pin "1") (pinfunction "1_1") (pintype "passive"))
      (node (ref "U3") (pin "1") (pinfunction "BIAS_1") (pintype "power_in"))
      (node (ref "U3") (pin "3") (pinfunction "IN_3") (pintype "power_in"))
      (node (ref "X-SOUTH") (pin "109") (pinfunction "109_109") (pintype "bidirectional"))
      (node (ref "X-SOUTH") (pin "115") (pinfunction "115_115") (pintype "bidirectional"))
      (node (ref "X-SOUTH") (pin "121") (pinfunction "121_121") (pintype "bidirectional"))
      (node (ref "X-SOUTH") (pin "127") (pinfunction "127_127") (pintype "bidirectional"))
      (node (ref "X-SOUTH") (pin "133") (pinfunction "133_133") (pintype "bidirectional"))
    )
    (net (code "251") (name "S_VW_CV") (class "Default")
      (node (ref "C13") (pin "1") (pinfunction "1_1") (pintype "passive"))
      (node (ref "R16") (pin "1") (pinfunction "1_1") (pintype "passive"))
      (node (ref "X-SOUTH") (pin "6") (pinfunction "6_6") (pintype "bidirectional"))
    )
    (net (code "252") (name "S_VW_OV") (class "Default")
      (node (ref "USW") (pin "7") (pinfunction "OUTB_7") (pintype "output"))
      (node (ref "X-SOUTH") (pin "5") (pinfunction "5_5") (pintype "bidirectional"))
    )
    (net (code "253") (name "S_VW_UV") (class "Default")
      (node (ref "USW") (pin "1") (pinfunction "OUTA_1") (pintype "output"))
      (node (ref "X-SOUTH") (pin "11") (pinfunction "11_11") (pintype "bidirectional"))
    )
    (net (code "254") (name "TDIG1") (class "Default")
      (node (ref "SENSOR") (pin "G27") (pinfunction "TDIG1_G27") (pintype "output"))
      (node (ref "U5") (pin "9") (pinfunction "B4_9") (pintype "bidirectional"))
    )
    (net (code "255") (name "TDIG2") (class "Default")
      (node (ref "SENSOR") (pin "G26") (pinfunction "TDIG2_G26") (pintype "output"))
      (node (ref "U6") (pin "11") (pinfunction "B2_11") (pintype "bidirectional"))
    )
    (net (code "256") (name "T_EXP1") (class "Default")
      (node (ref "SENSOR") (pin "H30") (pinfunction "T_EXP1_H30") (pintype "input"))
      (node (ref "U5") (pin "12") (pinfunction "B1_12") (pintype "bidirectional"))
    )
    (net (code "257") (name "T_EXP2") (class "Default")
      (node (ref "SENSOR") (pin "E29") (pinfunction "T_EXP2_E29") (pintype "input"))
      (node (ref "U6") (pin "10") (pinfunction "B3_10") (pintype "bidirectional"))
    )
    (net (code "258") (name "VRAMP1") (class "Default")
      (node (ref "C16") (pin "1") (pinfunction "1_1") (pintype "passive"))
      (node (ref "R23") (pin "1") (pinfunction "1_1") (pintype "passive"))
      (node (ref "SENSOR") (pin "G29") (pinfunction "VRAMP1_G29") (pintype "bidirectional"))
    )
    (net (code "259") (name "VRAMP2") (class "Default")
      (node (ref "C17") (pin "1") (pinfunction "1_1") (pintype "passive"))
      (node (ref "R23") (pin "2") (pinfunction "2_2") (pintype "passive"))
      (node (ref "SENSOR") (pin "F29") (pinfunction "VRAMP2_F29") (pintype "bidirectional"))
    )
    (net (code "260") (name "VTREF") (class "Default")
      (node (ref "C65") (pin "1") (pinfunction "1_1") (pintype "passive"))
      (node (ref "C91") (pin "2") (pinfunction "2_2") (pintype "passive"))
      (node (ref "R21") (pin "2") (pinfunction "2_2") (pintype "passive"))
      (node (ref "R24") (pin "1") (pinfunction "1_1") (pintype "passive"))
      (node (ref "SENSOR") (pin "B2") (pinfunction "VTREF_B2") (pintype "bidirectional"))
      (node (ref "U3") (pin "4") (pinfunction "OUT_4") (pintype "power_in"))
    )
    (net (code "261") (name "VTSIG") (class "Default")
      (node (ref "C66") (pin "1") (pinfunction "1_1") (pintype "passive"))
      (node (ref "R24") (pin "2") (pinfunction "2_2") (pintype "passive"))
      (node (ref "SENSOR") (pin "C2") (pinfunction "VTSIG_C2") (pintype "bidirectional"))
    )
    (net (code "262") (name "unconnected-(U1-NC-Pad2)") (class "Default")
      (node (ref "U1") (pin "2") (pinfunction "NC_2") (pintype "no_connect"))
    )
    (net (code "263") (name "unconnected-(U1-NC-Pad4)") (class "Default")
      (node (ref "U1") (pin "4") (pinfunction "NC_4") (pintype "no_connect"))
    )
    (net (code "264") (name "unconnected-(U1-NC-Pad5)") (class "Default")
      (node (ref "U1") (pin "5") (pinfunction "NC_5") (pintype "no_connect"))
    )
    (net (code "265") (name "unconnected-(U2-NC-Pad2)") (class "Default")
      (node (ref "U2") (pin "2") (pinfunction "NC_2") (pintype "no_connect"))
    )
    (net (code "266") (name "unconnected-(U2-NC-Pad4)") (class "Default")
      (node (ref "U2") (pin "4") (pinfunction "NC_4") (pintype "no_connect"))
    )
    (net (code "267") (name "unconnected-(U2-NC-Pad5)") (class "Default")
      (node (ref "U2") (pin "5") (pinfunction "NC_5") (pintype "no_connect"))
    )
    (net (code "268") (name "unconnected-(U7-OS-Pad3)") (class "Default")
      (node (ref "U7") (pin "3") (pinfunction "OS_3") (pintype "output"))
    )
    (net (code "269") (name "unconnected-(X-NORTH-PadM1)") (class "Default")
      (node (ref "X-NORTH") (pin "M1") (pinfunction "M1_M1") (pintype "bidirectional"))
    )
    (net (code "270") (name "unconnected-(X-NORTH-PadM2)") (class "Default")
      (node (ref "X-NORTH") (pin "M2") (pinfunction "M2_M2") (pintype "bidirectional"))
    )
    (net (code "271") (name "unconnected-(X-SOUTH-PadM1)") (class "Default")
      (node (ref "X-SOUTH") (pin "M1") (pinfunction "M1_M1") (pintype "bidirectional"))
    )
    (net (code "272") (name "unconnected-(X-SOUTH-PadM2)") (class "Default")
      (node (ref "X-SOUTH") (pin "M2") (pinfunction "M2_M2") (pintype "bidirectional"))
    )
  )
)
